# 02-Insence_interface.net
KiCad netlist of a schematic drawn in Altium Designer
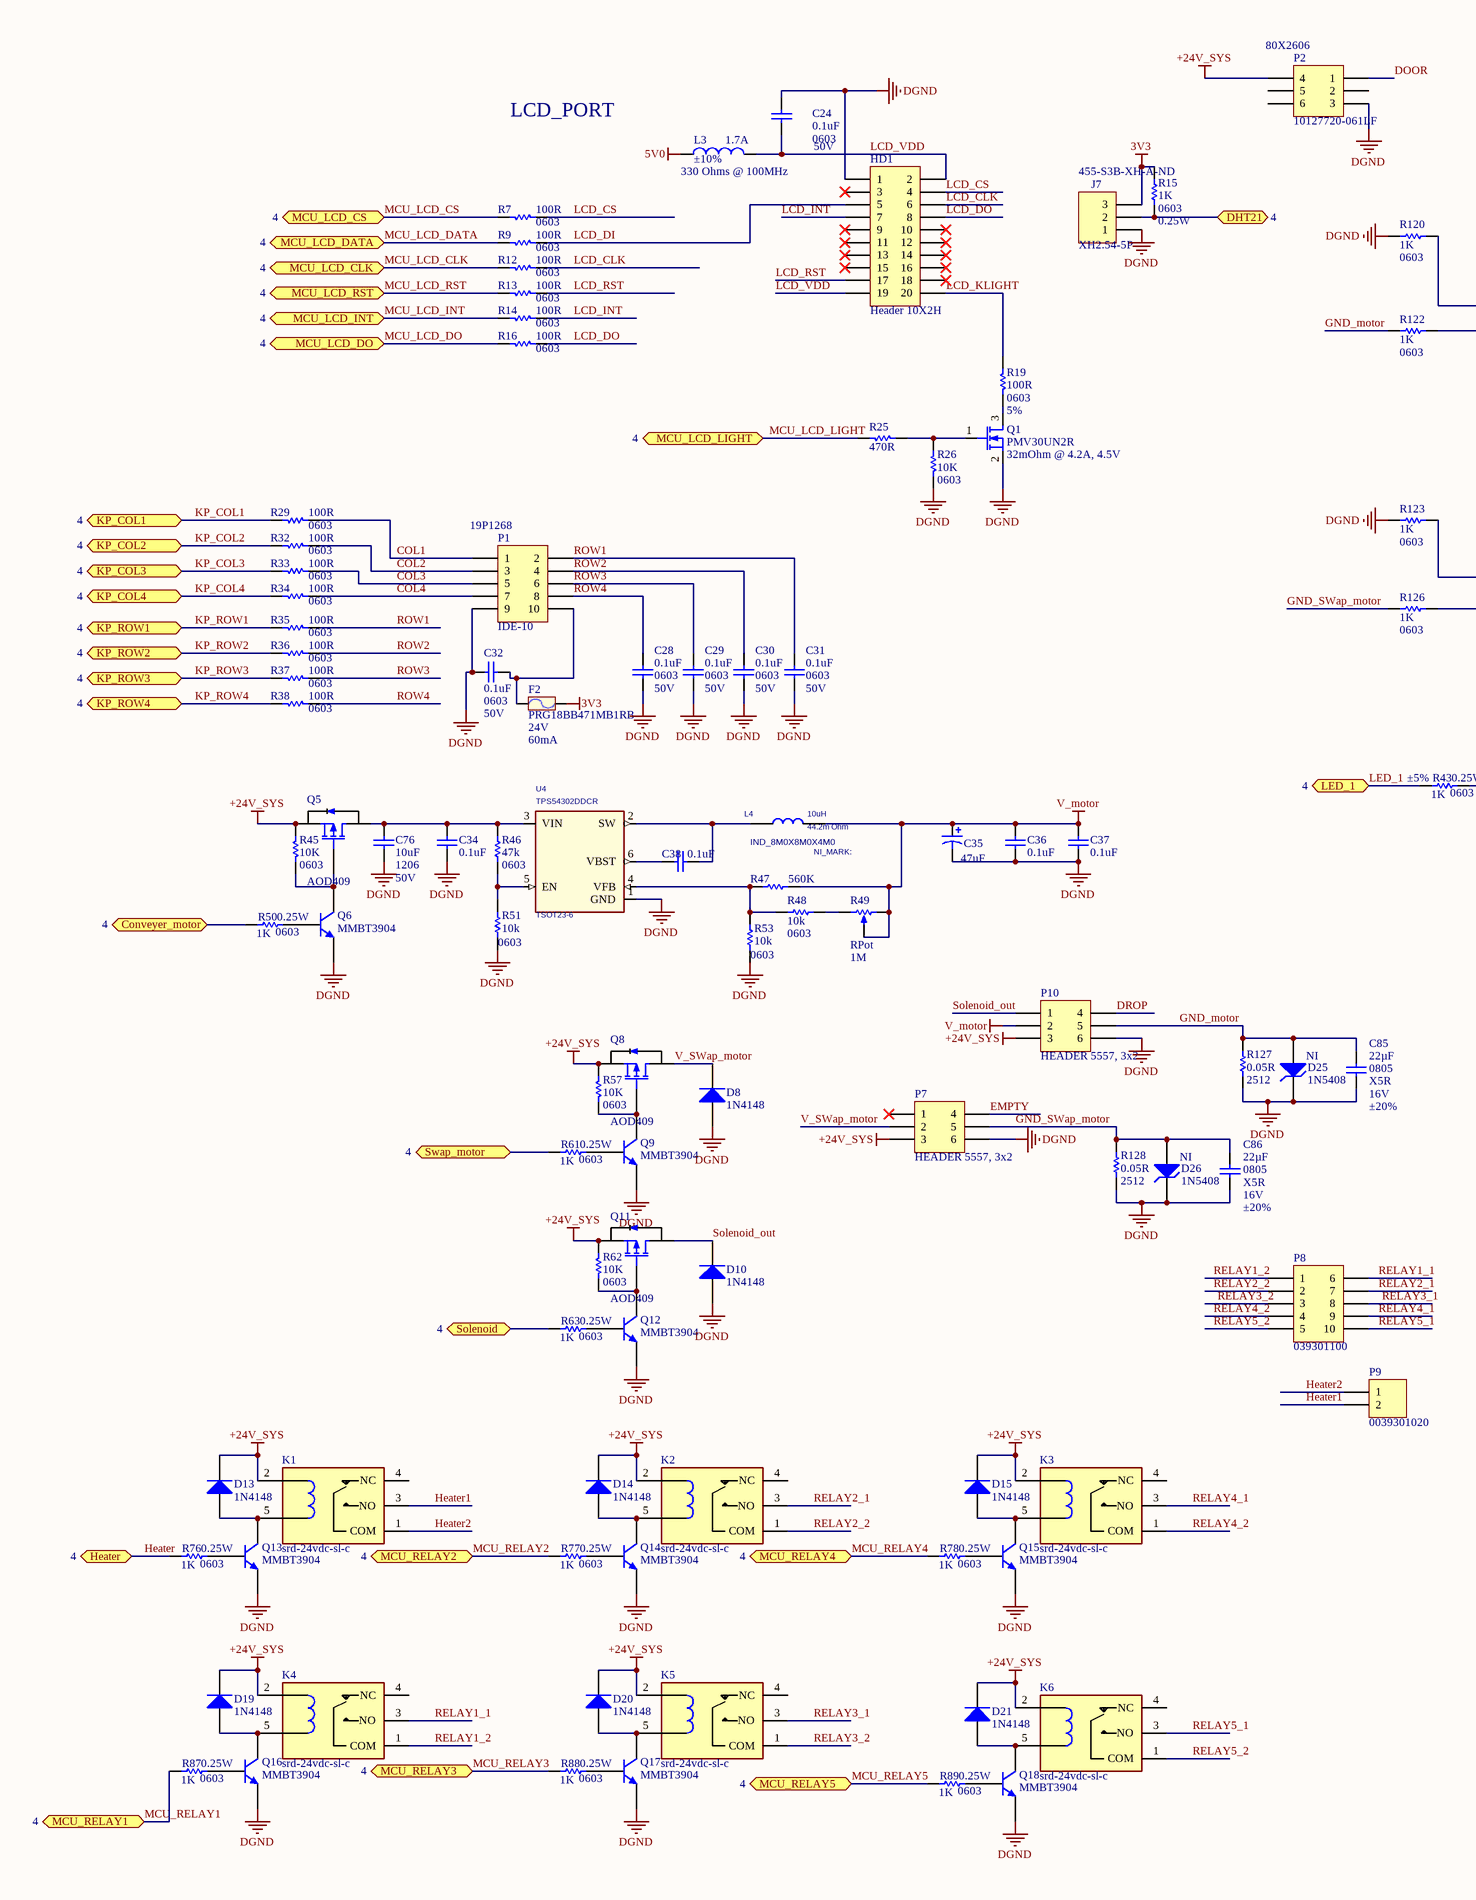
[diagram p0: 02-Insence_interface.SchDoc, left]
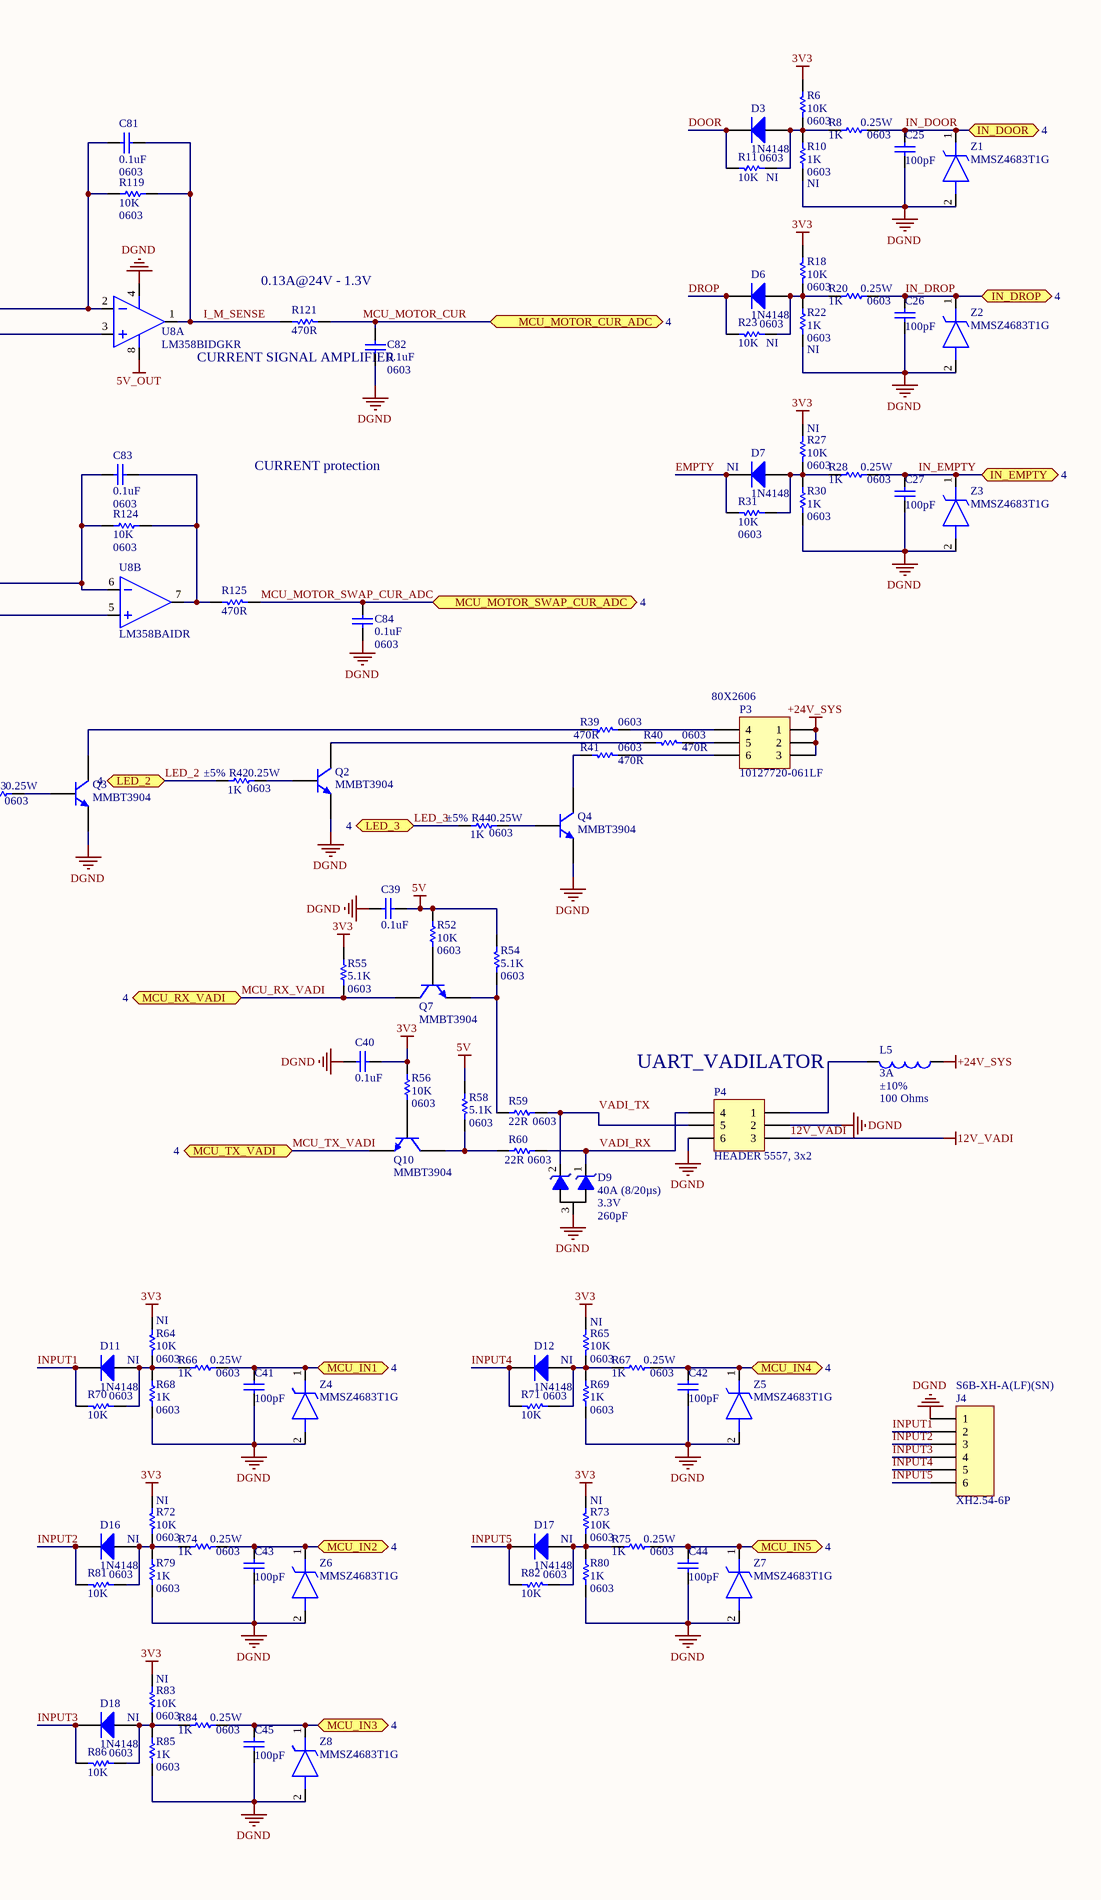
[diagram p1: 02-Insence_interface.SchDoc, right]

(export (version "E")
  (design (tool "Eeschema 10.0.6"))
  (components
    (comp (ref "C24")
      (value "0.1uF")
      (footprint "0603")
      (description "CAP CER 0.1UF 50V X7R 0603")
      (fields
        (field (name "MANUFACTURER1_PART#") "CL10B104KB8NNNC")
        (field (name "VOLTAGE") "50V")
        (field (name "TOLERANCE") "±10%")
      )
      (libsource (lib "thuvien") (part "Cap_0.1uF"))
    )
    (comp (ref "C25")
      (value "100pF")
      (footprint "CAP 0603")
      (description "CAP CER 100PF 50V C0G/NPO 0603")
      (fields (field (name "VOLTAGE") "50V") (field (name "TOLERANCE") "±10%"))
      (libsource (lib "Slider") (part "Cap"))
    )
    (comp (ref "C26")
      (value "100pF")
      (footprint "CAP 0603")
      (description "CAP CER 100PF 50V C0G/NPO 0603")
      (fields (field (name "VOLTAGE") "50V") (field (name "TOLERANCE") "±10%"))
      (libsource (lib "Slider") (part "Cap"))
    )
    (comp (ref "C27")
      (value "100pF")
      (footprint "CAP 0603")
      (description "CAP CER 100PF 50V C0G/NPO 0603")
      (fields (field (name "VOLTAGE") "50V") (field (name "TOLERANCE") "±10%"))
      (libsource (lib "Slider") (part "Cap"))
    )
    (comp (ref "C28")
      (value "0.1uF")
      (footprint "0603")
      (description "CAP CER 0.1UF 50V X7R 0603")
      (fields
        (field (name "MANUFACTURER1_PART#") "CL10B104KB8NNNC")
        (field (name "VOLTAGE") "50V")
        (field (name "TOLERANCE") "±10%")
      )
      (libsource (lib "thuvien") (part "Cap_0.1uF"))
    )
    (comp (ref "C29")
      (value "0.1uF")
      (footprint "0603")
      (description "CAP CER 0.1UF 50V X7R 0603")
      (fields
        (field (name "MANUFACTURER1_PART#") "CL10B104KB8NNNC")
        (field (name "VOLTAGE") "50V")
        (field (name "TOLERANCE") "±10%")
      )
      (libsource (lib "thuvien") (part "Cap_0.1uF"))
    )
    (comp (ref "C30")
      (value "0.1uF")
      (footprint "0603")
      (description "CAP CER 0.1UF 50V X7R 0603")
      (fields
        (field (name "MANUFACTURER1_PART#") "CL10B104KB8NNNC")
        (field (name "VOLTAGE") "50V")
        (field (name "TOLERANCE") "±10%")
      )
      (libsource (lib "thuvien") (part "Cap_0.1uF"))
    )
    (comp (ref "C31")
      (value "0.1uF")
      (footprint "0603")
      (description "CAP CER 0.1UF 50V X7R 0603")
      (fields
        (field (name "MANUFACTURER1_PART#") "CL10B104KB8NNNC")
        (field (name "VOLTAGE") "50V")
        (field (name "TOLERANCE") "±10%")
      )
      (libsource (lib "thuvien") (part "Cap_0.1uF"))
    )
    (comp (ref "C32")
      (value "0.1uF")
      (footprint "0603")
      (description "CAP CER 0.1UF 50V X7R 0603")
      (fields
        (field (name "MANUFACTURER1_PART#") "CL10B104KB8NNNC")
        (field (name "VOLTAGE") "50V")
        (field (name "TOLERANCE") "±10%")
      )
      (libsource (lib "thuvien") (part "Cap_0.1uF"))
    )
    (comp (ref "C34")
      (value "Cap")
      (footprint "0805")
      (description "CAP CER 0.1UF 50V X7R 0603")
      (fields
        (field (name "=VALUE") "0.1uF")
        (field (name "MANUFACTURER1_PART#") "CL10B104KB8NNNC")
        (field (name "PUBLISHER") "Altium Limited")
      )
      (libsource (lib "Miscellaneous Devices") (part "Cap"))
    )
    (comp (ref "C35")
      (value "47uF")
      (footprint "CAP ALUM SMD-D Package 6.3x5.4mm")
      (description "CAP ALUM 47UF 20% 35V SMD")
      (fields
        (field (name "MANUFACTURER1_PART#") "UUR1V470MCL6GS")
        (field (name "MANUFACTURER2_PART#") "EDK476M035A9GAA")
      )
      (libsource (lib "My Library") (part "Cap TANTAN 47UF35V2917"))
    )
    (comp (ref "C36")
      (value "Cap")
      (footprint "0805")
      (description "cap,0805,0.1uF,50V")
      (fields (field (name "=VALUE") "0.1uF") (field (name "PUBLISHER") "Altium Limited"))
      (libsource (lib "Miscellaneous Devices") (part "Cap"))
    )
    (comp (ref "C37")
      (value "Cap")
      (footprint "0805")
      (description "cap,0805,0.1uF,50V")
      (fields (field (name "=VALUE") "0.1uF") (field (name "PUBLISHER") "Altium Limited"))
      (libsource (lib "Miscellaneous Devices") (part "Cap"))
    )
    (comp (ref "C38")
      (value "Cap")
      (footprint "cap 0603")
      (description "CAP CER 0.1UF 50V X7R 0603")
      (fields
        (field (name "=VALUE") "0.1uF")
        (field (name "MANUFACTURER1_PART#") "CL10B104KB8NNNC")
        (field (name "PUBLISHER") "Altium Limited")
      )
      (libsource (lib "Miscellaneous Devices") (part "Cap"))
    )
    (comp (ref "C39")
      (value "0.1uF")
      (footprint "CAP 0603")
      (description "CAP CER 0.1UF 50V X7R 0603")
      (fields (field (name "VOLTAGE") "50V") (field (name "TOLERANCE") "±10%"))
      (libsource (lib "Slider") (part "Cap"))
    )
    (comp (ref "C40")
      (value "0.1uF")
      (footprint "CAP 0603")
      (description "CAP CER 0.1UF 50V X7R 0603")
      (fields (field (name "VOLTAGE") "50V") (field (name "TOLERANCE") "±10%"))
      (libsource (lib "Slider") (part "Cap"))
    )
    (comp (ref "C41")
      (value "100pF")
      (footprint "CAP 0603")
      (description "CAP CER 100PF 50V C0G/NPO 0603")
      (fields (field (name "VOLTAGE") "50V") (field (name "TOLERANCE") "±10%"))
      (libsource (lib "Slider") (part "Cap"))
    )
    (comp (ref "C42")
      (value "100pF")
      (footprint "CAP 0603")
      (description "CAP CER 100PF 50V C0G/NPO 0603")
      (fields (field (name "VOLTAGE") "50V") (field (name "TOLERANCE") "±10%"))
      (libsource (lib "Slider") (part "Cap"))
    )
    (comp (ref "C43")
      (value "100pF")
      (footprint "CAP 0603")
      (description "CAP CER 100PF 50V C0G/NPO 0603")
      (fields (field (name "VOLTAGE") "50V") (field (name "TOLERANCE") "±10%"))
      (libsource (lib "Slider") (part "Cap"))
    )
    (comp (ref "C44")
      (value "100pF")
      (footprint "CAP 0603")
      (description "CAP CER 100PF 50V C0G/NPO 0603")
      (fields (field (name "VOLTAGE") "50V") (field (name "TOLERANCE") "±10%"))
      (libsource (lib "Slider") (part "Cap"))
    )
    (comp (ref "C45")
      (value "100pF")
      (footprint "CAP 0603")
      (description "CAP CER 100PF 50V C0G/NPO 0603")
      (fields (field (name "VOLTAGE") "50V") (field (name "TOLERANCE") "±10%"))
      (libsource (lib "Slider") (part "Cap"))
    )
    (comp (ref "C76")
      (value "10uF")
      (footprint "1206")
      (description "CAP CER 10UF 50V X5R 1206")
      (fields
        (field (name "VOLTAGE") "50V")
        (field (name "TOLERANCE") "±10%")
        (field (name "MANUFACTURER1_PART#") "CL31A106MBHNNNE")
      )
      (libsource (lib "Slider") (part "Cap"))
    )
    (comp (ref "C81")
      (value "0.1uF")
      (footprint "0603")
      (description "CAP CER 0.1UF 50V X7R 0603")
      (fields (field (name "VOLTAGE") "50V") (field (name "TOLERANCE") "±10%"))
      (libsource (lib "Slider") (part "Cap"))
    )
    (comp (ref "C82")
      (value "0.1uF")
      (footprint "0603")
      (description "CAP CER 0.1UF 50V X7R 0603")
      (fields (field (name "VOLTAGE") "50V") (field (name "TOLERANCE") "±10%"))
      (libsource (lib "Slider") (part "Cap"))
    )
    (comp (ref "C83")
      (value "0.1uF")
      (footprint "0603")
      (description "CAP CER 0.1UF 50V X7R 0603")
      (fields (field (name "VOLTAGE") "50V") (field (name "TOLERANCE") "±10%"))
      (libsource (lib "Slider") (part "Cap"))
    )
    (comp (ref "C84")
      (value "0.1uF")
      (footprint "0603")
      (description "CAP CER 0.1UF 50V X7R 0603")
      (fields (field (name "VOLTAGE") "50V") (field (name "TOLERANCE") "±10%"))
      (libsource (lib "Slider") (part "Cap"))
    )
    (comp (ref "C85")
      (value "22µF")
      (footprint "CAP 0805")
      (description "CAP CER 22UF 16V X5R 0805")
      (fields
        (field (name "MANUFACTURER1_PART#") "CL21A226MOCLRNC")
        (field (name "MANUFACTURER2_PART#") "LMK212BBJ226MG-T")
        (field (name "PACKAGE") "0805")
        (field (name "VOLTAGE") "16V")
        (field (name "TOLERANCE") "±20%")
        (field (name "MATERIAL") "X5R")
      )
      (libsource (lib "Full") (part "Cap-NP-100"))
    )
    (comp (ref "C86")
      (value "22µF")
      (footprint "CAP 0805")
      (description "CAP CER 22UF 16V X5R 0805")
      (fields
        (field (name "MANUFACTURER1_PART#") "CL21A226MOCLRNC")
        (field (name "MANUFACTURER2_PART#") "LMK212BBJ226MG-T")
        (field (name "PACKAGE") "0805")
        (field (name "VOLTAGE") "16V")
        (field (name "TOLERANCE") "±20%")
        (field (name "MATERIAL") "X5R")
      )
      (libsource (lib "Full") (part "Cap-NP-100"))
    )
    (comp (ref "D3")
      (value "1N4148")
      (footprint "diode_1206")
      (description "DIODE GP 100V 300MA SOD123 10K")
      (fields
        (field (name "MANUFACTURER1_PART#") "1N4148WQ-13-F")
        (field (name "PUBLISHER") "Altium Limited")
      )
      (libsource (lib "Miscellaneous Devices") (part "Diode"))
    )
    (comp (ref "D6")
      (value "1N4148")
      (footprint "diode_1206")
      (description "DIODE GP 100V 300MA SOD123 10K")
      (fields
        (field (name "MANUFACTURER1_PART#") "1N4148WQ-13-F")
        (field (name "PUBLISHER") "Altium Limited")
      )
      (libsource (lib "Miscellaneous Devices") (part "Diode"))
    )
    (comp (ref "D7")
      (value "1N4148")
      (footprint "diode_1206")
      (description "DIODE GP 100V 300MA SOD123 10K")
      (fields
        (field (name "ASSEMBLY") "NI")
        (field (name "MANUFACTURER1_PART#") "1N4148WQ-13-F")
        (field (name "PUBLISHER") "Altium Limited")
      )
      (libsource (lib "Miscellaneous Devices") (part "Diode"))
    )
    (comp (ref "D8")
      (value "1N4148")
      (footprint "diode_1206")
      (description "DIODE GP 100V 300MA SOD123 10K")
      (fields
        (field (name "MANUFACTURER1_PART#") "1N4148WQ-13-F")
        (field (name "PUBLISHER") "Altium Limited")
      )
      (libsource (lib "Miscellaneous Devices") (part "Diode"))
    )
    (comp (ref "D9")
      (value "SM3.3H-TP")
      (footprint "SOT-23-3")
      (description "3.3V, ESD PROTECTION DEVICES, SO")
      (fields
        (field (name "CURRENT") "40A (8/20µs)")
        (field (name "MANUFACTURER2_PART#") "GSOT03C-E3-08")
        (field (name "POWER") "500W")
        (field (name "VOLTAGE") "3.3V")
        (field (name "JUNCTION CAPACITANCE") "260pF")
      )
      (libsource (lib "My Library") (part "TVS_DUAL_3V3_SOT23"))
    )
    (comp (ref "D10")
      (value "1N4148")
      (footprint "diode_1206")
      (description "DIODE GP 100V 300MA SOD123 10K")
      (fields
        (field (name "MANUFACTURER1_PART#") "1N4148WQ-13-F")
        (field (name "PUBLISHER") "Altium Limited")
      )
      (libsource (lib "Miscellaneous Devices") (part "Diode"))
    )
    (comp (ref "D11")
      (value "1N4148")
      (footprint "diode_1206")
      (description "DIODE GP 100V 300MA SOD123 10K")
      (fields
        (field (name "ASSEMBLY") "NI")
        (field (name "MANUFACTURER1_PART#") "1N4148WQ-13-F")
        (field (name "PUBLISHER") "Altium Limited")
      )
      (libsource (lib "Miscellaneous Devices") (part "Diode"))
    )
    (comp (ref "D12")
      (value "1N4148")
      (footprint "diode_1206")
      (description "DIODE GP 100V 300MA SOD123 10K")
      (fields
        (field (name "ASSEMBLY") "NI")
        (field (name "MANUFACTURER1_PART#") "1N4148WQ-13-F")
        (field (name "PUBLISHER") "Altium Limited")
      )
      (libsource (lib "Miscellaneous Devices") (part "Diode"))
    )
    (comp (ref "D13")
      (value "1N4148")
      (footprint "diode_1206")
      (description "DIODE GP 100V 300MA SOD123 10K")
      (fields
        (field (name "MANUFACTURER1_PART#") "1N4148WQ-13-F")
        (field (name "PUBLISHER") "Altium Limited")
      )
      (libsource (lib "Miscellaneous Devices") (part "Diode"))
    )
    (comp (ref "D14")
      (value "1N4148")
      (footprint "diode_1206")
      (description "DIODE GP 100V 300MA SOD123 10K")
      (fields
        (field (name "MANUFACTURER1_PART#") "1N4148WQ-13-F")
        (field (name "PUBLISHER") "Altium Limited")
      )
      (libsource (lib "Miscellaneous Devices") (part "Diode"))
    )
    (comp (ref "D15")
      (value "1N4148")
      (footprint "diode_1206")
      (description "DIODE GP 100V 300MA SOD123 10K")
      (fields
        (field (name "MANUFACTURER1_PART#") "1N4148WQ-13-F")
        (field (name "PUBLISHER") "Altium Limited")
      )
      (libsource (lib "Miscellaneous Devices") (part "Diode"))
    )
    (comp (ref "D16")
      (value "1N4148")
      (footprint "diode_1206")
      (description "DIODE GP 100V 300MA SOD123 10K")
      (fields
        (field (name "ASSEMBLY") "NI")
        (field (name "MANUFACTURER1_PART#") "1N4148WQ-13-F")
        (field (name "PUBLISHER") "Altium Limited")
      )
      (libsource (lib "Miscellaneous Devices") (part "Diode"))
    )
    (comp (ref "D17")
      (value "1N4148")
      (footprint "diode_1206")
      (description "DIODE GP 100V 300MA SOD123 10K")
      (fields
        (field (name "ASSEMBLY") "NI")
        (field (name "MANUFACTURER1_PART#") "1N4148WQ-13-F")
        (field (name "PUBLISHER") "Altium Limited")
      )
      (libsource (lib "Miscellaneous Devices") (part "Diode"))
    )
    (comp (ref "D18")
      (value "1N4148")
      (footprint "diode_1206")
      (description "DIODE GP 100V 300MA SOD123 10K")
      (fields
        (field (name "ASSEMBLY") "NI")
        (field (name "MANUFACTURER1_PART#") "1N4148WQ-13-F")
        (field (name "PUBLISHER") "Altium Limited")
      )
      (libsource (lib "Miscellaneous Devices") (part "Diode"))
    )
    (comp (ref "D19")
      (value "1N4148")
      (footprint "diode_1206")
      (description "DIODE GP 100V 300MA SOD123 10K")
      (fields
        (field (name "MANUFACTURER1_PART#") "1N4148WQ-13-F")
        (field (name "PUBLISHER") "Altium Limited")
      )
      (libsource (lib "Miscellaneous Devices") (part "Diode"))
    )
    (comp (ref "D20")
      (value "1N4148")
      (footprint "diode_1206")
      (description "DIODE GP 100V 300MA SOD123 10K")
      (fields
        (field (name "MANUFACTURER1_PART#") "1N4148WQ-13-F")
        (field (name "PUBLISHER") "Altium Limited")
      )
      (libsource (lib "Miscellaneous Devices") (part "Diode"))
    )
    (comp (ref "D21")
      (value "1N4148")
      (footprint "diode_1206")
      (description "DIODE GP 100V 300MA SOD123 10K")
      (fields
        (field (name "MANUFACTURER1_PART#") "1N4148WQ-13-F")
        (field (name "PUBLISHER") "Altium Limited")
      )
      (libsource (lib "Miscellaneous Devices") (part "Diode"))
    )
    (comp (ref "D25")
      (value "1N5408")
      (footprint "SMB")
      (description "TVS DIODE 30V 50.82V DO214AB")
      (fields (field (name "MANUFACTURER1_PART#") "S3MHE3_A/I") (field (name "NI_MARK") "NI"))
      (libsource (lib "My Library") (part "Diode Zener"))
    )
    (comp (ref "D26")
      (value "1N5408")
      (footprint "SMB")
      (description "TVS DIODE 30V 50.82V DO214AB")
      (fields (field (name "MANUFACTURER1_PART#") "S3MHE3_A/I") (field (name "NI_MARK") "NI"))
      (libsource (lib "My Library") (part "Diode Zener"))
    )
    (comp (ref "F2")
      (value "PRG18BB471MB1RB")
      (footprint "FB 0603")
      (description "PTC RESET FUSE 24V 10MA 0603")
      (fields (field (name "VOLTAGE - RATED") "24V") (field (name "CURRENT RATING (AMPS)") "60mA"))
      (libsource (lib "power acdc 12v 400mA V05") (part "0875.800MXEP"))
    )
    (comp (ref "HD1")
      (value "Header 10X2H")
      (footprint "IDE_20-RA")
      (description "CONN HEADER R/A 20POS 2.54MM")
      (fields (field (name "MANUFACTURER1_PART#") "61202021721") (field (name "PUBLISHER") "Altium Limited"))
      (libsource (lib "Miscellaneous Connectors") (part "Header 10X2H"))
    )
    (comp (ref "J4")
      (value "XH2.54-6P")
      (footprint "XH2.54-6P-RA")
      (description "CONN HEADER R/A 6POS 2.5MM")
      (fields
        (field (name "SUPPLIER PART NUMBER 1") "S6B-XH-A(LF)(SN)")
        (field (name "MANUFACTURER1_PART#") "S6B-XH-A")
        (field (name "PUBLISHER") "Altium Limited")
      )
      (libsource (lib "Miscellaneous Connectors") (part "Header 6"))
    )
    (comp (ref "J7")
      (value "XH2.54-5P")
      (footprint "XH2.54-3P-RA")
      (description "CONN HEADER R/A 3POS 2.5MM")
      (fields
        (field (name "SUPPLIER PART NUMBER 1") "455-S3B-XH-A-ND")
        (field (name "MANUFACTURER1_PART#") "S3B-XH-A")
        (field (name "PUBLISHER") "Altium Limited")
      )
      (libsource (lib "Miscellaneous Connectors") (part "Header 3"))
    )
    (comp (ref "K1")
      (value "srd-24vdc-sl-c")
      (footprint "Hiendv:srd24vdcslc")
      (description "Relay 24V 10A 5 PIN")
      (libsource (lib "lib") (part "srd-24vdc-sl-c"))
    )
    (comp (ref "K2")
      (value "srd-24vdc-sl-c")
      (footprint "Hiendv:srd24vdcslc")
      (description "Relay 24V 10A 5 PIN")
      (libsource (lib "lib") (part "srd-24vdc-sl-c"))
    )
    (comp (ref "K3")
      (value "srd-24vdc-sl-c")
      (footprint "Hiendv:srd24vdcslc")
      (description "Relay 24V 10A 5 PIN")
      (libsource (lib "lib") (part "srd-24vdc-sl-c"))
    )
    (comp (ref "K4")
      (value "srd-24vdc-sl-c")
      (footprint "Hiendv:srd24vdcslc")
      (description "Relay 24V 10A 5 PIN")
      (libsource (lib "lib") (part "srd-24vdc-sl-c"))
    )
    (comp (ref "K5")
      (value "srd-24vdc-sl-c")
      (footprint "Hiendv:srd24vdcslc")
      (description "Relay 24V 10A 5 PIN")
      (libsource (lib "lib") (part "srd-24vdc-sl-c"))
    )
    (comp (ref "K6")
      (value "srd-24vdc-sl-c")
      (footprint "Hiendv:srd24vdcslc")
      (description "Relay 24V 10A 5 PIN")
      (libsource (lib "lib") (part "srd-24vdc-sl-c"))
    )
    (comp (ref "L3")
      (value "330 Ohms @ 100MHz")
      (footprint "FB 0603")
      (description "FERRITE BEAD 330 OHM 0603 1LN")
      (fields
        (field (name "MANUFACTURER1_PART#") "MPZ1608S331ATA00")
        (field (name "MANUFACTURER2_PART#") "BLM18KG331SN1D")
        (field (name "CURRENT") "1.7A")
        (field (name "TOLERANCE") "±10%")
      )
      (libsource (lib "Full") (part "inductor 2.2uF"))
    )
    (comp (ref "L4")
      (value "10uH")
      (footprint "IND 8x8MM")
      (description "IND-SMD;10uH,20%,8x8x4mm,3.1A,44.2mOHM")
      (fields
        (field (name "PACKAGE") "IND_8M0X8M0X4M0")
        (field (name "TOLERANCE") "20%")
        (field (name "MFG1_PART#") "NR8040T100M")
        (field (name "DCR") "44.2m Ohm")
        (field (name "BY") "VINFAST_RD")
      )
      (libsource (lib "*") (part "IND_10uH_3.1A_44.2mOhm_8MX8MX4M"))
    )
    (comp (ref "L5")
      (value "100 Ohms")
      (footprint "FB 0603")
      (description "FERRITE BEAD 100 OHM 0603 1LN")
      (fields
        (field (name "MANUFACTURER1_PART#") "MPZ1608S101ATAH0")
        (field (name "MANUFACTURER2_PART#") "BLM18KG101TN1D")
        (field (name "CURRENT") "3A")
        (field (name "TOLERANCE") "±10%")
      )
      (libsource (lib "Full") (part "inductor 2.2uF"))
    )
    (comp (ref "P1")
      (value "IDE-10")
      (footprint "IDE-10-RA")
      (description "CONN HEADER R/A 10POS 2.54MM")
      (fields
        (field (name "MANUFACTURER1_PART#") "61201021721")
        (field (name "SUPPLIER PART NUMBER 1") "19P1268")
      )
      (libsource (lib "My Library") (part "IDE10"))
    )
    (comp (ref "P2")
      (value "10127720-061LF")
      (footprint "PHM-3x2H 3.0 - RA")
      (description "Header, 3-Pin, Dual row")
      (fields (field (name "SUPPLIER PART NUMBER 1") "80X2606") (field (name "PUBLISHER") "Altium Limited"))
      (libsource (lib "Miscellaneous Connectors") (part "Header 3X2A"))
    )
    (comp (ref "P3")
      (value "10127720-061LF")
      (footprint "PHM-3x2H 3.0 - RA")
      (description "Header, 3-Pin, Dual row")
      (fields (field (name "SUPPLIER PART NUMBER 1") "80X2606") (field (name "PUBLISHER") "Altium Limited"))
      (libsource (lib "Miscellaneous Connectors") (part "Header 3X2A"))
    )
    (comp (ref "P4")
      (value "HEADER 5557, 3x2")
      (footprint "HDR2x3 4_2MM FEMALE TH RA")
      (description "CONN HEADER R/A 6POS 4.2MM")
      (fields (field (name "MANUFACTURER1_PART#") "0039301060") (field (name "PUBLISHER") "Altium Limited"))
      (libsource (lib "Miscellaneous Connectors") (part "Header 3X2A"))
    )
    (comp (ref "P7")
      (value "HEADER 5557, 3x2")
      (footprint "HDR2x3 4_2MM FEMALE TH RA")
      (description "CONN HEADER R/A 6POS 4.2MM")
      (fields (field (name "MANUFACTURER1_PART#") "0039301060") (field (name "PUBLISHER") "Altium Limited"))
      (libsource (lib "") (part "Header 3X2A_1"))
    )
    (comp (ref "P8")
      (value "039301100")
      (footprint "HDR2x5 4_2MM FEMALE TH RA")
      (description "CONN HEADER R/A 10POS 4.2MM")
      (fields (field (name "PUBLISHER") "Altium Limited"))
      (libsource (lib "Miscellaneous Connectors") (part "Header 5X2A"))
    )
    (comp (ref "P9")
      (value "0039301020")
      (footprint "HDR2x1 4_2MM FEMALE TH RA")
      (description "Header, 2-Pin, Right Angle")
      (fields (field (name "PUBLISHER") "Altium Limited"))
      (libsource (lib "Miscellaneous Connectors") (part "Header 2H"))
    )
    (comp (ref "P10")
      (value "HEADER 5557, 3x2")
      (footprint "HDR2x3 4_2MM FEMALE TH RA")
      (description "CONN HEADER R/A 6POS 4.2MM")
      (fields (field (name "MANUFACTURER1_PART#") "0039301060") (field (name "PUBLISHER") "Altium Limited"))
      (libsource (lib "") (part "Header 3X2A_1"))
    )
    (comp (ref "Q1")
      (value "PMV30UN2R")
      (footprint "SOT-23-3")
      (description "MOSFET N-CH 20V 4.2A SOT23")
      (fields (field (name "RDSON") "32mOhm @ 4.2A, 4.5V"))
      (libsource (lib "VSM_SES-MAIN_REV04B") (part "Si2302DS"))
    )
    (comp (ref "Q2")
      (value "MMBT3904")
      (footprint "SOT-23")
      (description "NPN 200mA 40V 350mW SOT-23 Transistors")
      (libsource (lib "Miscellaneous Devices") (part "NPN"))
    )
    (comp (ref "Q3")
      (value "MMBT3904")
      (footprint "SOT-23")
      (description "NPN 200mA 40V 350mW SOT-23 Transistors")
      (libsource (lib "Miscellaneous Devices") (part "NPN"))
    )
    (comp (ref "Q4")
      (value "MMBT3904")
      (footprint "SOT-23")
      (description "NPN 200mA 40V 350mW SOT-23 Transistors")
      (libsource (lib "Miscellaneous Devices") (part "NPN"))
    )
    (comp (ref "Q5")
      (value "AOD409")
      (footprint "TO-252")
      (description "MOSFET P-CH 60V 26A TO252")
      (fields (field (name "PUBLISHER") "Altium Limited"))
      (libsource (lib "lib") (part "MOSFET-P"))
    )
    (comp (ref "Q6")
      (value "MMBT3904")
      (footprint "SOT-23")
      (description "NPN 200mA 40V 350mW SOT-23 Transistors")
      (libsource (lib "Miscellaneous Devices") (part "NPN"))
    )
    (comp (ref "Q7")
      (value "MMBT3904")
      (footprint "SOT-23")
      (description "NPN 200mA 40V 350mW SOT-23 Transistors")
      (libsource (lib "") (part "NPN_1"))
    )
    (comp (ref "Q8")
      (value "AOD409")
      (footprint "TO-252")
      (description "MOSFET P-CH 60V 26A TO252")
      (fields (field (name "PUBLISHER") "Altium Limited"))
      (libsource (lib "lib") (part "MOSFET-P"))
    )
    (comp (ref "Q9")
      (value "MMBT3904")
      (footprint "SOT-23")
      (description "NPN 200mA 40V 350mW SOT-23 Transistors")
      (libsource (lib "Miscellaneous Devices") (part "NPN"))
    )
    (comp (ref "Q10")
      (value "MMBT3904")
      (footprint "SOT-23")
      (description "NPN 200mA 40V 350mW SOT-23 Transistors")
      (libsource (lib "") (part "NPN_1"))
    )
    (comp (ref "Q11")
      (value "AOD409")
      (footprint "TO-252")
      (description "MOSFET P-CH 60V 26A TO252")
      (fields (field (name "PUBLISHER") "Altium Limited"))
      (libsource (lib "lib") (part "MOSFET-P"))
    )
    (comp (ref "Q12")
      (value "MMBT3904")
      (footprint "SOT-23")
      (description "NPN 200mA 40V 350mW SOT-23 Transistors")
      (libsource (lib "Miscellaneous Devices") (part "NPN"))
    )
    (comp (ref "Q13")
      (value "MMBT3904")
      (footprint "SOT-23")
      (description "NPN 200mA 40V 350mW SOT-23 Transistors")
      (libsource (lib "Miscellaneous Devices") (part "NPN"))
    )
    (comp (ref "Q14")
      (value "MMBT3904")
      (footprint "SOT-23")
      (description "NPN 200mA 40V 350mW SOT-23 Transistors")
      (libsource (lib "Miscellaneous Devices") (part "NPN"))
    )
    (comp (ref "Q15")
      (value "MMBT3904")
      (footprint "SOT-23")
      (description "NPN 200mA 40V 350mW SOT-23 Transistors")
      (libsource (lib "Miscellaneous Devices") (part "NPN"))
    )
    (comp (ref "Q16")
      (value "MMBT3904")
      (footprint "SOT-23")
      (description "NPN 200mA 40V 350mW SOT-23 Transistors")
      (libsource (lib "Miscellaneous Devices") (part "NPN"))
    )
    (comp (ref "Q17")
      (value "MMBT3904")
      (footprint "SOT-23")
      (description "NPN 200mA 40V 350mW SOT-23 Transistors")
      (libsource (lib "Miscellaneous Devices") (part "NPN"))
    )
    (comp (ref "Q18")
      (value "MMBT3904")
      (footprint "SOT-23")
      (description "NPN 200mA 40V 350mW SOT-23 Transistors")
      (libsource (lib "Miscellaneous Devices") (part "NPN"))
    )
    (comp (ref "R6")
      (value "10K")
      (footprint "res 0603")
      (description "RES SMD,10K OHM 5% 1/10W 0603")
      (fields
        (field (name "MANUFACTURER1_PART#") "RMCF0603JT10K0")
        (field (name "MANUFACTURER2_PART#") "R0603J10KKDX")
        (field (name "PCB FOOTPRINT") "0603")
      )
      (libsource (lib "altium-import") (part "root_3_mirrored_Res0.3_"))
    )
    (comp (ref "R7")
      (value "100R")
      (footprint "res 0603")
      (description "RES 100 OHM 5% 1/10W 0603")
      (fields (field (name "MANUFACTURER1_PART#") "RMCF0603JG100R") (field (name "PCB_ FOOTPRINT") "0603"))
      (libsource (lib "thuvien") (part "RES 120 OHM 5% 1/10W 0603"))
    )
    (comp (ref "R8")
      (value "1K")
      (footprint "res 0603")
      (description "RES SMD,1K OHM,5%,1/10W,0603")
      (fields
        (field (name "MANUFACTURER1_PART#") "RMCF06031K00JNEAC")
        (field (name "MANUFACTURER2_PART#") "R0603J1KTG")
        (field (name "PCB FOOTPRINT") "0603")
        (field (name "POWER") "0.25W")
      )
      (libsource (lib "Full") (part "Res0.3"))
    )
    (comp (ref "R9")
      (value "100R")
      (footprint "res 0603")
      (description "RES 100 OHM 5% 1/10W 0603")
      (fields (field (name "MANUFACTURER1_PART#") "RMCF0603JG100R") (field (name "PCB_ FOOTPRINT") "0603"))
      (libsource (lib "thuvien") (part "RES 120 OHM 5% 1/10W 0603"))
    )
    (comp (ref "R10")
      (value "1K")
      (footprint "res 0603")
      (description "RES SMD,1K OHM,5%,1/10W,0603")
      (fields
        (field (name "MANUFACTURER1_PART#") "RMCF06031K00JNEAC")
        (field (name "MANUFACTURER2_PART#") "R0603J1KTG")
        (field (name "PCB FOOTPRINT") "0603")
        (field (name "ASSEMBLY") "NI")
      )
      (libsource (lib "Full") (part "Res0.3"))
    )
    (comp (ref "R11")
      (value "10K")
      (footprint "res 0603")
      (description "RES SMD,10K OHM 5% 1/10W 0603")
      (fields
        (field (name "MANUFACTURER1_PART#") "RMCF0603JT10K0")
        (field (name "MANUFACTURER2_PART#") "R0603J10KKDX")
        (field (name "PCB FOOTPRINT") "0603")
        (field (name "ASSEMBLY") "NI")
      )
      (libsource (lib "altium-import") (part "root_2_mirrored_Res0.3_"))
    )
    (comp (ref "R12")
      (value "100R")
      (footprint "res 0603")
      (description "RES 100 OHM 5% 1/10W 0603")
      (fields (field (name "MANUFACTURER1_PART#") "RMCF0603JG100R") (field (name "PCB_ FOOTPRINT") "0603"))
      (libsource (lib "thuvien") (part "RES 120 OHM 5% 1/10W 0603"))
    )
    (comp (ref "R13")
      (value "100R")
      (footprint "res 0603")
      (description "RES 100 OHM 5% 1/10W 0603")
      (fields (field (name "MANUFACTURER1_PART#") "RMCF0603JG100R") (field (name "PCB_ FOOTPRINT") "0603"))
      (libsource (lib "thuvien") (part "RES 120 OHM 5% 1/10W 0603"))
    )
    (comp (ref "R14")
      (value "100R")
      (footprint "res 0603")
      (description "RES 100 OHM 5% 1/10W 0603")
      (fields (field (name "MANUFACTURER1_PART#") "RMCF0603JG100R") (field (name "PCB_ FOOTPRINT") "0603"))
      (libsource (lib "thuvien") (part "RES 120 OHM 5% 1/10W 0603"))
    )
    (comp (ref "R15")
      (value "1K")
      (footprint "res 0603")
      (description "RES SMD,1K OHM,5%,1/10W,0603")
      (fields
        (field (name "MANUFACTURER1_PART#") "RMCF06031K00JNEAC")
        (field (name "MANUFACTURER2_PART#") "R0603J1KTG")
        (field (name "PCB FOOTPRINT") "0603")
        (field (name "POWER") "0.25W")
      )
      (libsource (lib "Full") (part "Res0.3"))
    )
    (comp (ref "R16")
      (value "100R")
      (footprint "res 0603")
      (description "RES 100 OHM 5% 1/10W 0603")
      (fields (field (name "MANUFACTURER1_PART#") "RMCF0603JG100R") (field (name "PCB_ FOOTPRINT") "0603"))
      (libsource (lib "thuvien") (part "RES 120 OHM 5% 1/10W 0603"))
    )
    (comp (ref "R18")
      (value "10K")
      (footprint "res 0603")
      (description "RES SMD,10K OHM 5% 1/10W 0603")
      (fields
        (field (name "MANUFACTURER1_PART#") "RMCF0603JT10K0")
        (field (name "MANUFACTURER2_PART#") "R0603J10KKDX")
        (field (name "PCB FOOTPRINT") "0603")
      )
      (libsource (lib "altium-import") (part "root_3_mirrored_Res0.3_"))
    )
    (comp (ref "R19")
      (value "100R")
      (footprint "res 0603")
      (description "RES 100 OHM 5% 1/10W 0603")
      (fields
        (field (name "MANUFACTURER1_PART#") "RMCF0603JG100R")
        (field (name "PCB_ FOOTPRINT") "0603")
        (field (name "TOLERANCE") "5%")
      )
      (libsource (lib "thuvien") (part "RES 120 OHM 5% 1/10W 0603"))
    )
    (comp (ref "R20")
      (value "1K")
      (footprint "res 0603")
      (description "RES SMD,1K OHM,5%,1/10W,0603")
      (fields
        (field (name "MANUFACTURER1_PART#") "RMCF06031K00JNEAC")
        (field (name "MANUFACTURER2_PART#") "R0603J1KTG")
        (field (name "PCB FOOTPRINT") "0603")
        (field (name "POWER") "0.25W")
      )
      (libsource (lib "Full") (part "Res0.3"))
    )
    (comp (ref "R22")
      (value "1K")
      (footprint "res 0603")
      (description "RES SMD,1K OHM,5%,1/10W,0603")
      (fields
        (field (name "MANUFACTURER1_PART#") "RMCF06031K00JNEAC")
        (field (name "MANUFACTURER2_PART#") "R0603J1KTG")
        (field (name "PCB FOOTPRINT") "0603")
        (field (name "ASSEMBLY") "NI")
      )
      (libsource (lib "Full") (part "Res0.3"))
    )
    (comp (ref "R23")
      (value "10K")
      (footprint "res 0603")
      (description "RES SMD,10K OHM 5% 1/10W 0603")
      (fields
        (field (name "MANUFACTURER1_PART#") "RMCF0603JT10K0")
        (field (name "MANUFACTURER2_PART#") "R0603J10KKDX")
        (field (name "PCB FOOTPRINT") "0603")
        (field (name "ASSEMBLY") "NI")
      )
      (libsource (lib "altium-import") (part "root_2_mirrored_Res0.3_"))
    )
    (comp (ref "R25")
      (value "470R")
      (footprint "res 0603")
      (description "RES SMD, 470 OHM 5% 1/8W 0603")
      (fields
        (field (name "MANUFACTURER1_PART#") "RK73B1JTTD471J")
        (field (name "MANUFACTURER2_PART#") "RMCF0603JT470R")
      )
      (libsource (lib "Full") (part "Res0.3"))
    )
    (comp (ref "R26")
      (value "10K")
      (footprint "res 0603")
      (description "RES SMD,10K OHM 5% 1/10W 0603")
      (fields
        (field (name "MANUFACTURER1_PART#") "RMCF0603JT10K0")
        (field (name "MANUFACTURER2_PART#") "R0603J10KKDX")
        (field (name "PCB FOOTPRINT") "0603")
      )
      (libsource (lib "altium-import") (part "root_3_mirrored_Res0.3_"))
    )
    (comp (ref "R27")
      (value "10K")
      (footprint "res 0603")
      (description "RES SMD,10K OHM 5% 1/10W 0603")
      (fields
        (field (name "MANUFACTURER1_PART#") "RMCF0603JT10K0")
        (field (name "MANUFACTURER2_PART#") "R0603J10KKDX")
        (field (name "PCB FOOTPRINT") "0603")
        (field (name "ASEMBLY") "NI")
      )
      (libsource (lib "altium-import") (part "root_3_mirrored_Res0.3_"))
    )
    (comp (ref "R28")
      (value "1K")
      (footprint "res 0603")
      (description "RES SMD,1K OHM,5%,1/10W,0603")
      (fields
        (field (name "MANUFACTURER1_PART#") "RMCF06031K00JNEAC")
        (field (name "MANUFACTURER2_PART#") "R0603J1KTG")
        (field (name "PCB FOOTPRINT") "0603")
        (field (name "POWER") "0.25W")
      )
      (libsource (lib "Full") (part "Res0.3"))
    )
    (comp (ref "R29")
      (value "100R")
      (footprint "res 0603")
      (description "RES 100 OHM 5% 1/10W 0603")
      (fields (field (name "MANUFACTURER1_PART#") "RMCF0603JG100R") (field (name "PCB_ FOOTPRINT") "0603"))
      (libsource (lib "thuvien") (part "RES 120 OHM 5% 1/10W 0603"))
    )
    (comp (ref "R30")
      (value "1K")
      (footprint "res 0603")
      (description "RES SMD,1K OHM,5%,1/10W,0603")
      (fields
        (field (name "MANUFACTURER1_PART#") "RMCF06031K00JNEAC")
        (field (name "MANUFACTURER2_PART#") "R0603J1KTG")
        (field (name "PCB FOOTPRINT") "0603")
      )
      (libsource (lib "Full") (part "Res0.3"))
    )
    (comp (ref "R31")
      (value "10K")
      (footprint "res 0603")
      (description "RES SMD,10K OHM 5% 1/10W 0603")
      (fields
        (field (name "MANUFACTURER1_PART#") "RMCF0603JT10K0")
        (field (name "MANUFACTURER2_PART#") "R0603J10KKDX")
        (field (name "PCB FOOTPRINT") "0603")
      )
      (libsource (lib "altium-import") (part "root_2_mirrored_Res0.3_"))
    )
    (comp (ref "R32")
      (value "100R")
      (footprint "res 0603")
      (description "RES 100 OHM 5% 1/10W 0603")
      (fields (field (name "MANUFACTURER1_PART#") "RMCF0603JG100R") (field (name "PCB_ FOOTPRINT") "0603"))
      (libsource (lib "thuvien") (part "RES 120 OHM 5% 1/10W 0603"))
    )
    (comp (ref "R33")
      (value "100R")
      (footprint "res 0603")
      (description "RES 100 OHM 5% 1/10W 0603")
      (fields (field (name "MANUFACTURER1_PART#") "RMCF0603JG100R") (field (name "PCB_ FOOTPRINT") "0603"))
      (libsource (lib "thuvien") (part "RES 120 OHM 5% 1/10W 0603"))
    )
    (comp (ref "R34")
      (value "100R")
      (footprint "res 0603")
      (description "RES 100 OHM 5% 1/10W 0603")
      (fields (field (name "MANUFACTURER1_PART#") "RMCF0603JG100R") (field (name "PCB_ FOOTPRINT") "0603"))
      (libsource (lib "thuvien") (part "RES 120 OHM 5% 1/10W 0603"))
    )
    (comp (ref "R35")
      (value "100R")
      (footprint "res 0603")
      (description "RES 100 OHM 5% 1/10W 0603")
      (fields (field (name "MANUFACTURER1_PART#") "RMCF0603JG100R") (field (name "PCB_ FOOTPRINT") "0603"))
      (libsource (lib "thuvien") (part "RES 120 OHM 5% 1/10W 0603"))
    )
    (comp (ref "R36")
      (value "100R")
      (footprint "res 0603")
      (description "RES 100 OHM 5% 1/10W 0603")
      (fields (field (name "MANUFACTURER1_PART#") "RMCF0603JG100R") (field (name "PCB_ FOOTPRINT") "0603"))
      (libsource (lib "thuvien") (part "RES 120 OHM 5% 1/10W 0603"))
    )
    (comp (ref "R37")
      (value "100R")
      (footprint "res 0603")
      (description "RES 100 OHM 5% 1/10W 0603")
      (fields (field (name "MANUFACTURER1_PART#") "RMCF0603JG100R") (field (name "PCB_ FOOTPRINT") "0603"))
      (libsource (lib "thuvien") (part "RES 120 OHM 5% 1/10W 0603"))
    )
    (comp (ref "R38")
      (value "100R")
      (footprint "res 0603")
      (description "RES 100 OHM 5% 1/10W 0603")
      (fields (field (name "MANUFACTURER1_PART#") "RMCF0603JG100R") (field (name "PCB_ FOOTPRINT") "0603"))
      (libsource (lib "thuvien") (part "RES 120 OHM 5% 1/10W 0603"))
    )
    (comp (ref "R39")
      (value "470R")
      (footprint "res 0603")
      (description "RES SMD, 470 OHM 5% 1/8W 0603")
      (fields
        (field (name "MANUFACTURER1_PART#") "RK73B1JTTD471J")
        (field (name "MANUFACTURER2_PART#") "RMCF0603JT470R")
        (field (name "PCB FOOTPRINT") "0603")
      )
      (libsource (lib "Full") (part "Res0.3"))
    )
    (comp (ref "R40")
      (value "470R")
      (footprint "res 0603")
      (description "RES SMD, 470 OHM 5% 1/8W 0603")
      (fields
        (field (name "MANUFACTURER1_PART#") "RK73B1JTTD471J")
        (field (name "MANUFACTURER2_PART#") "RMCF0603JT470R")
        (field (name "PCB FOOTPRINT") "0603")
      )
      (libsource (lib "Full") (part "Res0.3"))
    )
    (comp (ref "R41")
      (value "470R")
      (footprint "res 0603")
      (description "RES SMD, 470 OHM 5% 1/8W 0603")
      (fields
        (field (name "MANUFACTURER1_PART#") "RK73B1JTTD471J")
        (field (name "MANUFACTURER2_PART#") "RMCF0603JT470R")
        (field (name "PCB FOOTPRINT") "0603")
      )
      (libsource (lib "Full") (part "Res0.3"))
    )
    (comp (ref "R42")
      (value "1K")
      (footprint "res 0603")
      (description "RES SMD,1K OHM,5%,1/10W,0603")
      (fields
        (field (name "MANUFACTURER1_PART#") "RMCF06031K00JNEAC")
        (field (name "MANUFACTURER2_PART#") "R0603J1KTG")
        (field (name "PCB FOOTPRINT") "0603")
        (field (name "POWER") "0.25W")
        (field (name "TOLERANCE") "±5%")
      )
      (libsource (lib "Full") (part "Res0.3"))
    )
    (comp (ref "R43")
      (value "1K")
      (footprint "res 0603")
      (description "RES SMD,1K OHM,5%,1/10W,0603")
      (fields
        (field (name "MANUFACTURER1_PART#") "RMCF06031K00JNEAC")
        (field (name "MANUFACTURER2_PART#") "R0603J1KTG")
        (field (name "PCB FOOTPRINT") "0603")
        (field (name "POWER") "0.25W")
        (field (name "TOLERANCE") "±5%")
      )
      (libsource (lib "Full") (part "Res0.3"))
    )
    (comp (ref "R44")
      (value "1K")
      (footprint "res 0603")
      (description "RES SMD,1K OHM,5%,1/10W,0603")
      (fields
        (field (name "MANUFACTURER1_PART#") "RMCF06031K00JNEAC")
        (field (name "MANUFACTURER2_PART#") "R0603J1KTG")
        (field (name "PCB FOOTPRINT") "0603")
        (field (name "POWER") "0.25W")
        (field (name "TOLERANCE") "±5%")
      )
      (libsource (lib "Full") (part "Res0.3"))
    )
    (comp (ref "R45")
      (value "10K")
      (footprint "res 0603")
      (description "RES SMD,10K OHM 5% 1/10W 0603")
      (fields
        (field (name "MANUFACTURER1_PART#") "RMCF0603JT10K0")
        (field (name "MANUFACTURER2_PART#") "R0603J10KKDX")
        (field (name "PCB FOOTPRINT") "0603")
      )
      (libsource (lib "altium-import") (part "root_3_mirrored_Res0.3_"))
    )
    (comp (ref "R46")
      (value "47k")
      (footprint "0603")
      (description "RES 47K OHM 5% 1/10W 0603")
      (fields
        (field (name "MANUFACTURER1_PART#") "RMCF0603JT47K0")
        (field (name "Comment") "Res1")
        (field (name "PUBLISHER") "Altium Limited")
      )
      (libsource (lib "Miscellaneous Devices") (part "Res1"))
    )
    (comp (ref "R47")
      (value "560K")
      (footprint "res 0603")
      (description "RES 560K OHM 1% 1/10W 0603")
      (fields
        (field (name "MANUFACTURER1_PART#") "RC0603FR-07560KL")
        (field (name "Comment") "Res1")
        (field (name "PUBLISHER") "Altium Limited")
      )
      (libsource (lib "Miscellaneous Devices") (part "Res1"))
    )
    (comp (ref "R48")
      (value "10k")
      (footprint "0603")
      (description "RES SMD,10K OHM 5% 1/10W 0603")
      (fields
        (field (name "MANUFACTURER1_PART#") "RMCF0603JT10K0")
        (field (name "Comment") "Res1")
        (field (name "PUBLISHER") "Altium Limited")
      )
      (libsource (lib "Miscellaneous Devices") (part "Res1"))
    )
    (comp (ref "R49")
      (value "RPot")
      (footprint "VR5")
      (description "VR 105-1M 3296W")
      (fields (field (name "ALTIUM_VALUE") "1M") (field (name "PUBLISHER") "Altium Limited"))
      (libsource (lib "Miscellaneous Devices") (part "RPot"))
    )
    (comp (ref "R50")
      (value "1K")
      (footprint "res 0603")
      (description "RES SMD,1K OHM,5%,1/10W,0603")
      (fields
        (field (name "MANUFACTURER1_PART#") "RMCF06031K00JNEAC")
        (field (name "MANUFACTURER2_PART#") "R0603J1KTG")
        (field (name "PCB FOOTPRINT") "0603")
        (field (name "POWER") "0.25W")
      )
      (libsource (lib "Full") (part "Res0.3"))
    )
    (comp (ref "R51")
      (value "10k")
      (footprint "0603")
      (description "RES SMD,10K OHM 5% 1/10W 0603")
      (fields
        (field (name "MANUFACTURER1_PART#") "RMCF0603JT10K0")
        (field (name "Comment") "Res1")
        (field (name "PUBLISHER") "Altium Limited")
      )
      (libsource (lib "Miscellaneous Devices") (part "Res1"))
    )
    (comp (ref "R52")
      (value "10K")
      (footprint "res 0603")
      (description "RES SMD,10K OHM 5% 1/10W 0603")
      (fields
        (field (name "MANUFACTURER1_PART#") "RMCF0603JT10K0")
        (field (name "MANUFACTURER2_PART#") "R0603J10KKDX")
        (field (name "PCB FOOTPRINT") "0603")
      )
      (libsource (lib "altium-import") (part "root_3_Res0.3_"))
    )
    (comp (ref "R53")
      (value "10k")
      (footprint "0603")
      (description "RES SMD,10K OHM 5% 1/10W 0603")
      (fields
        (field (name "MANUFACTURER1_PART#") "RMCF0603JT10K0")
        (field (name "Comment") "Res1")
        (field (name "PUBLISHER") "Altium Limited")
      )
      (libsource (lib "Miscellaneous Devices") (part "Res1"))
    )
    (comp (ref "R54")
      (value "5.1K")
      (footprint "res 0603")
      (description "RES SMD 5.1K OHM 1% 1/10W 0603")
      (fields (field (name "MANUFACTURER1_PART#") "RC0603FR-075K1L") (field (name "PCB FOOTPRINT") "0603"))
      (libsource (lib "Full") (part "Res0.3"))
    )
    (comp (ref "R55")
      (value "5.1K")
      (footprint "res 0603")
      (description "RES SMD 5.1K OHM 1% 1/10W 0603")
      (fields (field (name "MANUFACTURER1_PART#") "RC0603FR-075K1L") (field (name "PCB FOOTPRINT") "0603"))
      (libsource (lib "Full") (part "Res0.3"))
    )
    (comp (ref "R56")
      (value "10K")
      (footprint "res 0603")
      (description "RES SMD,10K OHM 5% 1/10W 0603")
      (fields
        (field (name "MANUFACTURER1_PART#") "RMCF0603JT10K0")
        (field (name "MANUFACTURER2_PART#") "R0603J10KKDX")
        (field (name "PCB FOOTPRINT") "0603")
      )
      (libsource (lib "altium-import") (part "root_3_Res0.3_"))
    )
    (comp (ref "R57")
      (value "10K")
      (footprint "res 0603")
      (description "RES SMD,10K OHM 5% 1/10W 0603")
      (fields
        (field (name "MANUFACTURER1_PART#") "RMCF0603JT10K0")
        (field (name "MANUFACTURER2_PART#") "R0603J10KKDX")
        (field (name "PCB FOOTPRINT") "0603")
      )
      (libsource (lib "altium-import") (part "root_3_mirrored_Res0.3_"))
    )
    (comp (ref "R58")
      (value "5.1K")
      (footprint "res 0603")
      (description "RES SMD 5.1K OHM 1% 1/10W 0603")
      (fields (field (name "MANUFACTURER1_PART#") "RC0603FR-075K1L") (field (name "PCB FOOTPRINT") "0603"))
      (libsource (lib "Full") (part "Res0.3"))
    )
    (comp (ref "R59")
      (value "22R")
      (footprint "res 0603")
      (description "RES 22 OHM 5% 1/10W 0603")
      (fields
        (field (name "MANUFACTURER1_PART#") "RC0603JR-0722RL")
        (field (name "MANUFACTURER2_PART#") "RMCF0603JT22R0")
        (field (name "PCB FOOTPRINT") "0603")
      )
      (libsource (lib "Full") (part "Res0.3"))
    )
    (comp (ref "R60")
      (value "22R")
      (footprint "res 0603")
      (description "RES 22 OHM 5% 1/10W 0603")
      (fields
        (field (name "MANUFACTURER1_PART#") "RC0603JR-0722RL")
        (field (name "MANUFACTURER2_PART#") "RMCF0603JT22R0")
        (field (name "PCB FOOTPRINT") "0603")
      )
      (libsource (lib "Full") (part "Res0.3"))
    )
    (comp (ref "R61")
      (value "1K")
      (footprint "res 0603")
      (description "RES SMD,1K OHM,5%,1/10W,0603")
      (fields
        (field (name "MANUFACTURER1_PART#") "RMCF06031K00JNEAC")
        (field (name "MANUFACTURER2_PART#") "R0603J1KTG")
        (field (name "PCB FOOTPRINT") "0603")
        (field (name "POWER") "0.25W")
      )
      (libsource (lib "Full") (part "Res0.3"))
    )
    (comp (ref "R62")
      (value "10K")
      (footprint "res 0603")
      (description "RES SMD,10K OHM 5% 1/10W 0603")
      (fields
        (field (name "MANUFACTURER1_PART#") "RMCF0603JT10K0")
        (field (name "MANUFACTURER2_PART#") "R0603J10KKDX")
        (field (name "PCB FOOTPRINT") "0603")
      )
      (libsource (lib "altium-import") (part "root_3_mirrored_Res0.3_"))
    )
    (comp (ref "R63")
      (value "1K")
      (footprint "res 0603")
      (description "RES SMD,1K OHM,5%,1/10W,0603")
      (fields
        (field (name "MANUFACTURER1_PART#") "RMCF06031K00JNEAC")
        (field (name "MANUFACTURER2_PART#") "R0603J1KTG")
        (field (name "PCB FOOTPRINT") "0603")
        (field (name "POWER") "0.25W")
      )
      (libsource (lib "Full") (part "Res0.3"))
    )
    (comp (ref "R64")
      (value "10K")
      (footprint "res 0603")
      (description "RES SMD,10K OHM 5% 1/10W 0603")
      (fields
        (field (name "MANUFACTURER1_PART#") "RMCF0603JT10K0")
        (field (name "MANUFACTURER2_PART#") "R0603J10KKDX")
        (field (name "PCB FOOTPRINT") "0603")
        (field (name "ASSEMBLY") "NI")
      )
      (libsource (lib "altium-import") (part "root_3_mirrored_Res0.3_"))
    )
    (comp (ref "R65")
      (value "10K")
      (footprint "res 0603")
      (description "RES SMD,10K OHM 5% 1/10W 0603")
      (fields
        (field (name "MANUFACTURER1_PART#") "RMCF0603JT10K0")
        (field (name "MANUFACTURER2_PART#") "R0603J10KKDX")
        (field (name "PCB FOOTPRINT") "0603")
        (field (name "ASSEMBLY") "NI")
      )
      (libsource (lib "altium-import") (part "root_3_mirrored_Res0.3_"))
    )
    (comp (ref "R66")
      (value "1K")
      (footprint "res 0603")
      (description "RES SMD,1K OHM,5%,1/10W,0603")
      (fields
        (field (name "MANUFACTURER1_PART#") "RMCF06031K00JNEAC")
        (field (name "MANUFACTURER2_PART#") "R0603J1KTG")
        (field (name "PCB FOOTPRINT") "0603")
        (field (name "POWER") "0.25W")
      )
      (libsource (lib "Full") (part "Res0.3"))
    )
    (comp (ref "R67")
      (value "1K")
      (footprint "res 0603")
      (description "RES SMD,1K OHM,5%,1/10W,0603")
      (fields
        (field (name "MANUFACTURER1_PART#") "RMCF06031K00JNEAC")
        (field (name "MANUFACTURER2_PART#") "R0603J1KTG")
        (field (name "PCB FOOTPRINT") "0603")
        (field (name "POWER") "0.25W")
      )
      (libsource (lib "Full") (part "Res0.3"))
    )
    (comp (ref "R68")
      (value "1K")
      (footprint "res 0603")
      (description "RES SMD,1K OHM,5%,1/10W,0603")
      (fields
        (field (name "MANUFACTURER1_PART#") "RMCF06031K00JNEAC")
        (field (name "MANUFACTURER2_PART#") "R0603J1KTG")
        (field (name "PCB FOOTPRINT") "0603")
      )
      (libsource (lib "Full") (part "Res0.3"))
    )
    (comp (ref "R69")
      (value "1K")
      (footprint "res 0603")
      (description "RES SMD,1K OHM,5%,1/10W,0603")
      (fields
        (field (name "MANUFACTURER1_PART#") "RMCF06031K00JNEAC")
        (field (name "MANUFACTURER2_PART#") "R0603J1KTG")
        (field (name "PCB FOOTPRINT") "0603")
      )
      (libsource (lib "Full") (part "Res0.3"))
    )
    (comp (ref "R70")
      (value "10K")
      (footprint "res 0603")
      (description "RES SMD,10K OHM 5% 1/10W 0603")
      (fields
        (field (name "MANUFACTURER1_PART#") "RMCF0603JT10K0")
        (field (name "MANUFACTURER2_PART#") "R0603J10KKDX")
        (field (name "PCB FOOTPRINT") "0603")
      )
      (libsource (lib "altium-import") (part "root_2_mirrored_Res0.3_"))
    )
    (comp (ref "R71")
      (value "10K")
      (footprint "res 0603")
      (description "RES SMD,10K OHM 5% 1/10W 0603")
      (fields
        (field (name "MANUFACTURER1_PART#") "RMCF0603JT10K0")
        (field (name "MANUFACTURER2_PART#") "R0603J10KKDX")
        (field (name "PCB FOOTPRINT") "0603")
      )
      (libsource (lib "altium-import") (part "root_2_mirrored_Res0.3_"))
    )
    (comp (ref "R72")
      (value "10K")
      (footprint "res 0603")
      (description "RES SMD,10K OHM 5% 1/10W 0603")
      (fields
        (field (name "MANUFACTURER1_PART#") "RMCF0603JT10K0")
        (field (name "MANUFACTURER2_PART#") "R0603J10KKDX")
        (field (name "PCB FOOTPRINT") "0603")
        (field (name "ASSEMBLY") "NI")
      )
      (libsource (lib "altium-import") (part "root_3_mirrored_Res0.3_"))
    )
    (comp (ref "R73")
      (value "10K")
      (footprint "res 0603")
      (description "RES SMD,10K OHM 5% 1/10W 0603")
      (fields
        (field (name "MANUFACTURER1_PART#") "RMCF0603JT10K0")
        (field (name "MANUFACTURER2_PART#") "R0603J10KKDX")
        (field (name "PCB FOOTPRINT") "0603")
        (field (name "ASSEMBLY") "NI")
      )
      (libsource (lib "altium-import") (part "root_3_mirrored_Res0.3_"))
    )
    (comp (ref "R74")
      (value "1K")
      (footprint "res 0603")
      (description "RES SMD,1K OHM,5%,1/10W,0603")
      (fields
        (field (name "MANUFACTURER1_PART#") "RMCF06031K00JNEAC")
        (field (name "MANUFACTURER2_PART#") "R0603J1KTG")
        (field (name "PCB FOOTPRINT") "0603")
        (field (name "POWER") "0.25W")
      )
      (libsource (lib "Full") (part "Res0.3"))
    )
    (comp (ref "R75")
      (value "1K")
      (footprint "res 0603")
      (description "RES SMD,1K OHM,5%,1/10W,0603")
      (fields
        (field (name "MANUFACTURER1_PART#") "RMCF06031K00JNEAC")
        (field (name "MANUFACTURER2_PART#") "R0603J1KTG")
        (field (name "PCB FOOTPRINT") "0603")
        (field (name "POWER") "0.25W")
      )
      (libsource (lib "Full") (part "Res0.3"))
    )
    (comp (ref "R76")
      (value "1K")
      (footprint "res 0603")
      (description "RES SMD,1K OHM,5%,1/10W,0603")
      (fields
        (field (name "MANUFACTURER1_PART#") "RMCF06031K00JNEAC")
        (field (name "MANUFACTURER2_PART#") "R0603J1KTG")
        (field (name "PCB FOOTPRINT") "0603")
        (field (name "POWER") "0.25W")
      )
      (libsource (lib "Full") (part "Res0.3"))
    )
    (comp (ref "R77")
      (value "1K")
      (footprint "res 0603")
      (description "RES SMD,1K OHM,5%,1/10W,0603")
      (fields
        (field (name "MANUFACTURER1_PART#") "RMCF06031K00JNEAC")
        (field (name "MANUFACTURER2_PART#") "R0603J1KTG")
        (field (name "PCB FOOTPRINT") "0603")
        (field (name "POWER") "0.25W")
      )
      (libsource (lib "Full") (part "Res0.3"))
    )
    (comp (ref "R78")
      (value "1K")
      (footprint "res 0603")
      (description "RES SMD,1K OHM,5%,1/10W,0603")
      (fields
        (field (name "MANUFACTURER1_PART#") "RMCF06031K00JNEAC")
        (field (name "MANUFACTURER2_PART#") "R0603J1KTG")
        (field (name "PCB FOOTPRINT") "0603")
        (field (name "POWER") "0.25W")
      )
      (libsource (lib "Full") (part "Res0.3"))
    )
    (comp (ref "R79")
      (value "1K")
      (footprint "res 0603")
      (description "RES SMD,1K OHM,5%,1/10W,0603")
      (fields
        (field (name "MANUFACTURER1_PART#") "RMCF06031K00JNEAC")
        (field (name "MANUFACTURER2_PART#") "R0603J1KTG")
        (field (name "PCB FOOTPRINT") "0603")
      )
      (libsource (lib "Full") (part "Res0.3"))
    )
    (comp (ref "R80")
      (value "1K")
      (footprint "res 0603")
      (description "RES SMD,1K OHM,5%,1/10W,0603")
      (fields
        (field (name "MANUFACTURER1_PART#") "RMCF06031K00JNEAC")
        (field (name "MANUFACTURER2_PART#") "R0603J1KTG")
        (field (name "PCB FOOTPRINT") "0603")
      )
      (libsource (lib "Full") (part "Res0.3"))
    )
    (comp (ref "R81")
      (value "10K")
      (footprint "res 0603")
      (description "RES SMD,10K OHM 5% 1/10W 0603")
      (fields
        (field (name "MANUFACTURER1_PART#") "RMCF0603JT10K0")
        (field (name "MANUFACTURER2_PART#") "R0603J10KKDX")
        (field (name "PCB FOOTPRINT") "0603")
      )
      (libsource (lib "altium-import") (part "root_2_mirrored_Res0.3_"))
    )
    (comp (ref "R82")
      (value "10K")
      (footprint "res 0603")
      (description "RES SMD,10K OHM 5% 1/10W 0603")
      (fields
        (field (name "MANUFACTURER1_PART#") "RMCF0603JT10K0")
        (field (name "MANUFACTURER2_PART#") "R0603J10KKDX")
        (field (name "PCB FOOTPRINT") "0603")
      )
      (libsource (lib "altium-import") (part "root_2_mirrored_Res0.3_"))
    )
    (comp (ref "R83")
      (value "10K")
      (footprint "res 0603")
      (description "RES SMD,10K OHM 5% 1/10W 0603")
      (fields
        (field (name "MANUFACTURER1_PART#") "RMCF0603JT10K0")
        (field (name "MANUFACTURER2_PART#") "R0603J10KKDX")
        (field (name "PCB FOOTPRINT") "0603")
        (field (name "ASSEMBLY") "NI")
      )
      (libsource (lib "altium-import") (part "root_3_mirrored_Res0.3_"))
    )
    (comp (ref "R84")
      (value "1K")
      (footprint "res 0603")
      (description "RES SMD,1K OHM,5%,1/10W,0603")
      (fields
        (field (name "MANUFACTURER1_PART#") "RMCF06031K00JNEAC")
        (field (name "MANUFACTURER2_PART#") "R0603J1KTG")
        (field (name "PCB FOOTPRINT") "0603")
        (field (name "POWER") "0.25W")
      )
      (libsource (lib "Full") (part "Res0.3"))
    )
    (comp (ref "R85")
      (value "1K")
      (footprint "res 0603")
      (description "RES SMD,1K OHM,5%,1/10W,0603")
      (fields
        (field (name "MANUFACTURER1_PART#") "RMCF06031K00JNEAC")
        (field (name "MANUFACTURER2_PART#") "R0603J1KTG")
        (field (name "PCB FOOTPRINT") "0603")
      )
      (libsource (lib "Full") (part "Res0.3"))
    )
    (comp (ref "R86")
      (value "10K")
      (footprint "res 0603")
      (description "RES SMD,10K OHM 5% 1/10W 0603")
      (fields
        (field (name "MANUFACTURER1_PART#") "RMCF0603JT10K0")
        (field (name "MANUFACTURER2_PART#") "R0603J10KKDX")
        (field (name "PCB FOOTPRINT") "0603")
      )
      (libsource (lib "altium-import") (part "root_2_mirrored_Res0.3_"))
    )
    (comp (ref "R87")
      (value "1K")
      (footprint "res 0603")
      (description "RES SMD,1K OHM,5%,1/10W,0603")
      (fields
        (field (name "MANUFACTURER1_PART#") "RMCF06031K00JNEAC")
        (field (name "MANUFACTURER2_PART#") "R0603J1KTG")
        (field (name "PCB FOOTPRINT") "0603")
        (field (name "POWER") "0.25W")
      )
      (libsource (lib "Full") (part "Res0.3"))
    )
    (comp (ref "R88")
      (value "1K")
      (footprint "res 0603")
      (description "RES SMD,1K OHM,5%,1/10W,0603")
      (fields
        (field (name "MANUFACTURER1_PART#") "RMCF06031K00JNEAC")
        (field (name "MANUFACTURER2_PART#") "R0603J1KTG")
        (field (name "PCB FOOTPRINT") "0603")
        (field (name "POWER") "0.25W")
      )
      (libsource (lib "Full") (part "Res0.3"))
    )
    (comp (ref "R89")
      (value "1K")
      (footprint "res 0603")
      (description "RES SMD,1K OHM,5%,1/10W,0603")
      (fields
        (field (name "MANUFACTURER1_PART#") "RMCF06031K00JNEAC")
        (field (name "MANUFACTURER2_PART#") "R0603J1KTG")
        (field (name "PCB FOOTPRINT") "0603")
        (field (name "POWER") "0.25W")
      )
      (libsource (lib "Full") (part "Res0.3"))
    )
    (comp (ref "R119")
      (value "10K")
      (footprint "res 0603")
      (description "RES SMD,10K OHM 5% 1/10W 0603")
      (fields
        (field (name "MANUFACTURER1_PART#") "RMCF0603JT10K0")
        (field (name "MANUFACTURER2_PART#") "R0603J10KKDX")
        (field (name "PCB FOOTPRINT") "0603")
      )
      (libsource (lib "altium-import") (part "root_0_Res0.3_"))
    )
    (comp (ref "R120")
      (value "1K")
      (footprint "res 0603")
      (description "RES SMD,1K OHM,5%,1/10W,0603")
      (fields
        (field (name "MANUFACTURER1_PART#") "RMCF06031K00JNEAC")
        (field (name "MANUFACTURER2_PART#") "R0603J1KTG")
        (field (name "PCB FOOTPRINT") "0603")
      )
      (libsource (lib "Full") (part "Res0.3"))
    )
    (comp (ref "R121")
      (value "470R")
      (footprint "res 0603")
      (description "RES SMD, 470 OHM 5% 1/8W 0603")
      (fields
        (field (name "MANUFACTURER1_PART#") "RK73B1JTTD471J")
        (field (name "MANUFACTURER2_PART#") "RMCF0603JT470R")
      )
      (libsource (lib "Full") (part "Res0.3"))
    )
    (comp (ref "R122")
      (value "1K")
      (footprint "res 0603")
      (description "RES SMD,1K OHM,5%,1/10W,0603")
      (fields
        (field (name "MANUFACTURER1_PART#") "RMCF06031K00JNEAC")
        (field (name "MANUFACTURER2_PART#") "R0603J1KTG")
        (field (name "PCB FOOTPRINT") "0603")
      )
      (libsource (lib "Full") (part "Res0.3"))
    )
    (comp (ref "R123")
      (value "1K")
      (footprint "res 0603")
      (description "RES SMD,1K OHM,5%,1/10W,0603")
      (fields
        (field (name "MANUFACTURER1_PART#") "RMCF06031K00JNEAC")
        (field (name "MANUFACTURER2_PART#") "R0603J1KTG")
        (field (name "PCB FOOTPRINT") "0603")
      )
      (libsource (lib "Full") (part "Res0.3"))
    )
    (comp (ref "R124")
      (value "10K")
      (footprint "res 0603")
      (description "RES SMD,10K OHM 5% 1/10W 0603")
      (fields
        (field (name "MANUFACTURER1_PART#") "RMCF0603JT10K0")
        (field (name "MANUFACTURER2_PART#") "R0603J10KKDX")
        (field (name "PCB FOOTPRINT") "0603")
      )
      (libsource (lib "altium-import") (part "root_0_Res0.3_"))
    )
    (comp (ref "R125")
      (value "470R")
      (footprint "res 0603")
      (description "RES SMD, 470 OHM 5% 1/8W 0603")
      (fields
        (field (name "MANUFACTURER1_PART#") "RK73B1JTTD471J")
        (field (name "MANUFACTURER2_PART#") "RMCF0603JT470R")
      )
      (libsource (lib "Full") (part "Res0.3"))
    )
    (comp (ref "R126")
      (value "1K")
      (footprint "res 0603")
      (description "RES SMD,1K OHM,5%,1/10W,0603")
      (fields
        (field (name "MANUFACTURER1_PART#") "RMCF06031K00JNEAC")
        (field (name "MANUFACTURER2_PART#") "R0603J1KTG")
        (field (name "PCB FOOTPRINT") "0603")
      )
      (libsource (lib "Full") (part "Res0.3"))
    )
    (comp (ref "R127")
      (value "0.05R")
      (footprint "res 2512")
      (description "RES SMD 0.05 OHM 1% 1W 2512")
      (fields
        (field (name "MANUFACTURER1_PART#") "TLRP3A30CR050FTE")
        (field (name "MANUFACTURER2_PART#") "https://banlinhkien.com/tro-2512-1-r0500.05r-1w-p6652906.html")
        (field (name "PCB FOOTPRINT") "2512")
      )
      (libsource (lib "Full") (part "Res0.3"))
    )
    (comp (ref "R128")
      (value "0.05R")
      (footprint "res 2512")
      (description "RES SMD 0.05 OHM 1% 1W 2512")
      (fields
        (field (name "MANUFACTURER1_PART#") "TLRP3A30CR050FTE")
        (field (name "MANUFACTURER2_PART#") "https://banlinhkien.com/tro-2512-1-r0500.05r-1w-p6652906.html")
        (field (name "PCB FOOTPRINT") "2512")
      )
      (libsource (lib "Full") (part "Res0.3"))
    )
    (comp (ref "U4")
      (value "TPS54302DDCR")
      (footprint "SOT23-6")
      (description "IC REG BUCK ADJ 3A TSOT23-6,TPS54302DDCR")
      (fields
        (field (name "DISTR1_PART#") "296-46237-1-ND")
        (field (name "PACKAGE") "TSOT23-6")
        (field (name "BY") "VINFAST_RD")
      )
      (libsource (lib "*") (part "IC_TPS54302DDCR"))
    )
    (comp (ref "U8")
      (value "LM358BIDGKR")
      (footprint "SOIC-8")
      (description "IC OPAMP GP 2 CIRCUIT 8SOIC")
      (fields
        (field (name "MANUFACTURER2_PART#") "LM358DR2G")
        (field (name "MANUFACTURER1_PART#") "LM358BAIDR")
      )
      (libsource (lib "VSM") (part "LM358"))
    )
    (comp (ref "Z1")
      (value "MMSZ4683T1G")
      (footprint "Hiendv:SOD3716X135N")
      (description "DIODE ZENER 3V 500MW SOD123")
      (fields (field (name "MOUSER PART NUMBER") "863-MMSZ4683T1G"))
      (libsource (lib "*") (part "MMSZ4683T1G"))
    )
    (comp (ref "Z2")
      (value "MMSZ4683T1G")
      (footprint "Hiendv:SOD3716X135N")
      (description "DIODE ZENER 3V 500MW SOD123")
      (fields (field (name "MOUSER PART NUMBER") "863-MMSZ4683T1G"))
      (libsource (lib "*") (part "MMSZ4683T1G"))
    )
    (comp (ref "Z3")
      (value "MMSZ4683T1G")
      (footprint "Hiendv:SOD3716X135N")
      (description "DIODE ZENER 3V 500MW SOD123")
      (fields (field (name "MOUSER PART NUMBER") "863-MMSZ4683T1G"))
      (libsource (lib "*") (part "MMSZ4683T1G"))
    )
    (comp (ref "Z4")
      (value "MMSZ4683T1G")
      (footprint "Hiendv:SOD3716X135N")
      (description "DIODE ZENER 3V 500MW SOD123")
      (fields (field (name "MOUSER PART NUMBER") "863-MMSZ4683T1G"))
      (libsource (lib "*") (part "MMSZ4683T1G"))
    )
    (comp (ref "Z5")
      (value "MMSZ4683T1G")
      (footprint "Hiendv:SOD3716X135N")
      (description "DIODE ZENER 3V 500MW SOD123")
      (fields (field (name "MOUSER PART NUMBER") "863-MMSZ4683T1G"))
      (libsource (lib "*") (part "MMSZ4683T1G"))
    )
    (comp (ref "Z6")
      (value "MMSZ4683T1G")
      (footprint "Hiendv:SOD3716X135N")
      (description "DIODE ZENER 3V 500MW SOD123")
      (fields (field (name "MOUSER PART NUMBER") "863-MMSZ4683T1G"))
      (libsource (lib "*") (part "MMSZ4683T1G"))
    )
    (comp (ref "Z7")
      (value "MMSZ4683T1G")
      (footprint "Hiendv:SOD3716X135N")
      (description "DIODE ZENER 3V 500MW SOD123")
      (fields (field (name "MOUSER PART NUMBER") "863-MMSZ4683T1G"))
      (libsource (lib "*") (part "MMSZ4683T1G"))
    )
    (comp (ref "Z8")
      (value "MMSZ4683T1G")
      (footprint "Hiendv:SOD3716X135N")
      (description "DIODE ZENER 3V 500MW SOD123")
      (fields (field (name "MOUSER PART NUMBER") "863-MMSZ4683T1G"))
      (libsource (lib "*") (part "MMSZ4683T1G"))
    )
  )
  (nets
    (net (code "1") (name "+24V_SYS") (class "Default")
      (node (ref "D13") (pin "2") (pinfunction "K_2") (pintype "passive"))
      (node (ref "D14") (pin "2") (pinfunction "K_2") (pintype "passive"))
      (node (ref "D15") (pin "2") (pinfunction "K_2") (pintype "passive"))
      (node (ref "D19") (pin "2") (pinfunction "K_2") (pintype "passive"))
      (node (ref "D20") (pin "2") (pinfunction "K_2") (pintype "passive"))
      (node (ref "D21") (pin "2") (pinfunction "K_2") (pintype "passive"))
      (node (ref "K1") (pin "2") (pinfunction "COIL_1_2") (pintype "passive"))
      (node (ref "K2") (pin "2") (pinfunction "COIL_1_2") (pintype "passive"))
      (node (ref "K3") (pin "2") (pinfunction "COIL_1_2") (pintype "passive"))
      (node (ref "K4") (pin "2") (pinfunction "COIL_1_2") (pintype "passive"))
      (node (ref "K5") (pin "2") (pinfunction "COIL_1_2") (pintype "passive"))
      (node (ref "K6") (pin "2") (pinfunction "COIL_1_2") (pintype "passive"))
      (node (ref "L5") (pin "1") (pinfunction "1_1") (pintype "passive"))
      (node (ref "P10") (pin "3") (pinfunction "3_3") (pintype "passive"))
      (node (ref "P2") (pin "4") (pinfunction "4_4") (pintype "passive"))
      (node (ref "P3") (pin "1") (pinfunction "1_1") (pintype "passive"))
      (node (ref "P3") (pin "2") (pinfunction "2_2") (pintype "passive"))
      (node (ref "P3") (pin "3") (pinfunction "3_3") (pintype "passive"))
      (node (ref "P7") (pin "3") (pinfunction "3_3") (pintype "passive"))
      (node (ref "Q11") (pin "3") (pinfunction "S_3") (pintype "passive"))
      (node (ref "Q5") (pin "3") (pinfunction "S_3") (pintype "passive"))
      (node (ref "Q8") (pin "3") (pinfunction "S_3") (pintype "passive"))
      (node (ref "R45") (pin "1") (pinfunction "1_1") (pintype "passive"))
      (node (ref "R57") (pin "1") (pinfunction "1_1") (pintype "passive"))
      (node (ref "R62") (pin "1") (pinfunction "1_1") (pintype "passive"))
    )
    (net (code "2") (name "/COL1") (class "Default")
      (node (ref "P1") (pin "1") (pinfunction "1_1") (pintype "passive"))
      (node (ref "R29") (pin "2") (pinfunction "2_2") (pintype "passive"))
    )
    (net (code "3") (name "/COL2") (class "Default")
      (node (ref "P1") (pin "3") (pinfunction "3_3") (pintype "passive"))
      (node (ref "R32") (pin "2") (pinfunction "2_2") (pintype "passive"))
    )
    (net (code "4") (name "/COL3") (class "Default")
      (node (ref "P1") (pin "5") (pinfunction "5_5") (pintype "passive"))
      (node (ref "R33") (pin "2") (pinfunction "2_2") (pintype "passive"))
    )
    (net (code "5") (name "/COL4") (class "Default")
      (node (ref "P1") (pin "7") (pinfunction "7_7") (pintype "passive"))
      (node (ref "R34") (pin "2") (pinfunction "2_2") (pintype "passive"))
    )
    (net (code "6") (name "/Conveyer_motor") (class "Default")
      (node (ref "R50") (pin "2") (pinfunction "2_2") (pintype "passive"))
    )
    (net (code "7") (name "/DHT21") (class "Default")
      (node (ref "J7") (pin "2") (pinfunction "2_2") (pintype "passive"))
      (node (ref "R15") (pin "1") (pinfunction "1_1") (pintype "passive"))
    )
    (net (code "8") (name "/DOOR") (class "Default")
      (node (ref "D3") (pin "2") (pinfunction "K_2") (pintype "passive"))
      (node (ref "P2") (pin "1") (pinfunction "1_1") (pintype "passive"))
      (node (ref "R11") (pin "1") (pinfunction "1_1") (pintype "passive"))
    )
    (net (code "9") (name "/DROP") (class "Default")
      (node (ref "D6") (pin "2") (pinfunction "K_2") (pintype "passive"))
      (node (ref "P10") (pin "4") (pinfunction "4_4") (pintype "passive"))
      (node (ref "R23") (pin "1") (pinfunction "1_1") (pintype "passive"))
    )
    (net (code "10") (name "/EMPTY") (class "Default")
      (node (ref "D7") (pin "2") (pinfunction "K_2") (pintype "passive"))
      (node (ref "P7") (pin "4") (pinfunction "4_4") (pintype "passive"))
      (node (ref "R31") (pin "1") (pinfunction "1_1") (pintype "passive"))
    )
    (net (code "11") (name "/GND_SWap_motor") (class "Default")
      (node (ref "C86") (pin "1") (pinfunction "1_1") (pintype "passive"))
      (node (ref "D26") (pin "1") (pinfunction "A_1") (pintype "passive"))
      (node (ref "P7") (pin "5") (pinfunction "5_5") (pintype "passive"))
      (node (ref "R126") (pin "2") (pinfunction "2_2") (pintype "passive"))
      (node (ref "R128") (pin "1") (pinfunction "1_1") (pintype "passive"))
    )
    (net (code "12") (name "/GND_motor") (class "Default")
      (node (ref "C85") (pin "1") (pinfunction "1_1") (pintype "passive"))
      (node (ref "D25") (pin "1") (pinfunction "A_1") (pintype "passive"))
      (node (ref "P10") (pin "5") (pinfunction "5_5") (pintype "passive"))
      (node (ref "R122") (pin "2") (pinfunction "2_2") (pintype "passive"))
      (node (ref "R127") (pin "1") (pinfunction "1_1") (pintype "passive"))
    )
    (net (code "13") (name "/Heater") (class "Default")
      (node (ref "R76") (pin "2") (pinfunction "2_2") (pintype "passive"))
    )
    (net (code "14") (name "/Heater1") (class "Default")
      (node (ref "K1") (pin "3") (pinfunction "NO_3") (pintype "passive"))
      (node (ref "P9") (pin "2") (pinfunction "2_2") (pintype "passive"))
    )
    (net (code "15") (name "/Heater2") (class "Default")
      (node (ref "K1") (pin "1") (pinfunction "COM_1") (pintype "passive"))
      (node (ref "P9") (pin "1") (pinfunction "1_1") (pintype "passive"))
    )
    (net (code "16") (name "/INPUT1") (class "Default")
      (node (ref "D11") (pin "2") (pinfunction "K_2") (pintype "passive"))
      (node (ref "J4") (pin "2") (pinfunction "2_2") (pintype "passive"))
      (node (ref "R70") (pin "1") (pinfunction "1_1") (pintype "passive"))
    )
    (net (code "17") (name "/INPUT2") (class "Default")
      (node (ref "D16") (pin "2") (pinfunction "K_2") (pintype "passive"))
      (node (ref "J4") (pin "3") (pinfunction "3_3") (pintype "passive"))
      (node (ref "R81") (pin "1") (pinfunction "1_1") (pintype "passive"))
    )
    (net (code "18") (name "/INPUT3") (class "Default")
      (node (ref "D18") (pin "2") (pinfunction "K_2") (pintype "passive"))
      (node (ref "J4") (pin "4") (pinfunction "4_4") (pintype "passive"))
      (node (ref "R86") (pin "1") (pinfunction "1_1") (pintype "passive"))
    )
    (net (code "19") (name "/INPUT4") (class "Default")
      (node (ref "D12") (pin "2") (pinfunction "K_2") (pintype "passive"))
      (node (ref "J4") (pin "5") (pinfunction "5_5") (pintype "passive"))
      (node (ref "R71") (pin "1") (pinfunction "1_1") (pintype "passive"))
    )
    (net (code "20") (name "/INPUT5") (class "Default")
      (node (ref "D17") (pin "2") (pinfunction "K_2") (pintype "passive"))
      (node (ref "J4") (pin "6") (pinfunction "6_6") (pintype "passive"))
      (node (ref "R82") (pin "1") (pinfunction "1_1") (pintype "passive"))
    )
    (net (code "21") (name "/IN_DOOR") (class "Default")
      (node (ref "C25") (pin "2") (pinfunction "2_2") (pintype "passive"))
      (node (ref "R8") (pin "1") (pinfunction "1_1") (pintype "passive"))
      (node (ref "Z1") (pin "1") (pinfunction "K_1") (pintype "passive"))
    )
    (net (code "22") (name "/IN_DROP") (class "Default")
      (node (ref "C26") (pin "2") (pinfunction "2_2") (pintype "passive"))
      (node (ref "R20") (pin "1") (pinfunction "1_1") (pintype "passive"))
      (node (ref "Z2") (pin "1") (pinfunction "K_1") (pintype "passive"))
    )
    (net (code "23") (name "/IN_EMPTY") (class "Default")
      (node (ref "C27") (pin "2") (pinfunction "2_2") (pintype "passive"))
      (node (ref "R28") (pin "1") (pinfunction "1_1") (pintype "passive"))
      (node (ref "Z3") (pin "1") (pinfunction "K_1") (pintype "passive"))
    )
    (net (code "24") (name "/I_M_SENSE") (class "Default")
      (node (ref "C81") (pin "1") (pinfunction "1_1") (pintype "passive"))
      (node (ref "R119") (pin "2") (pinfunction "2_2") (pintype "passive"))
      (node (ref "R121") (pin "1") (pinfunction "1_1") (pintype "passive"))
      (node (ref "U8") (pin "1") (pinfunction "OUT_1") (pintype "passive"))
    )
    (net (code "25") (name "/KP_COL1") (class "Default")
      (node (ref "R29") (pin "1") (pinfunction "1_1") (pintype "passive"))
    )
    (net (code "26") (name "/KP_COL2") (class "Default")
      (node (ref "R32") (pin "1") (pinfunction "1_1") (pintype "passive"))
    )
    (net (code "27") (name "/KP_COL3") (class "Default")
      (node (ref "R33") (pin "1") (pinfunction "1_1") (pintype "passive"))
    )
    (net (code "28") (name "/KP_COL4") (class "Default")
      (node (ref "R34") (pin "1") (pinfunction "1_1") (pintype "passive"))
    )
    (net (code "29") (name "/KP_ROW1") (class "Default")
      (node (ref "R35") (pin "1") (pinfunction "1_1") (pintype "passive"))
    )
    (net (code "30") (name "/KP_ROW2") (class "Default")
      (node (ref "R36") (pin "1") (pinfunction "1_1") (pintype "passive"))
    )
    (net (code "31") (name "/KP_ROW3") (class "Default")
      (node (ref "R37") (pin "1") (pinfunction "1_1") (pintype "passive"))
    )
    (net (code "32") (name "/KP_ROW4") (class "Default")
      (node (ref "R38") (pin "1") (pinfunction "1_1") (pintype "passive"))
    )
    (net (code "33") (name "/LCD_CLK") (class "Default")
      (node (ref "HD1") (pin "6") (pinfunction "6_6") (pintype "passive"))
      (node (ref "R12") (pin "2") (pinfunction "2_2") (pintype "passive"))
    )
    (net (code "34") (name "/LCD_CS") (class "Default")
      (node (ref "HD1") (pin "4") (pinfunction "4_4") (pintype "passive"))
      (node (ref "R7") (pin "2") (pinfunction "2_2") (pintype "passive"))
    )
    (net (code "35") (name "/LCD_DI") (class "Default")
      (node (ref "HD1") (pin "5") (pinfunction "5_5") (pintype "passive"))
      (node (ref "R9") (pin "2") (pinfunction "2_2") (pintype "passive"))
    )
    (net (code "36") (name "/LCD_DO") (class "Default")
      (node (ref "HD1") (pin "8") (pinfunction "8_8") (pintype "passive"))
      (node (ref "R16") (pin "2") (pinfunction "2_2") (pintype "passive"))
    )
    (net (code "37") (name "/LCD_INT") (class "Default")
      (node (ref "HD1") (pin "7") (pinfunction "7_7") (pintype "passive"))
      (node (ref "R14") (pin "2") (pinfunction "2_2") (pintype "passive"))
    )
    (net (code "38") (name "/LCD_KLIGHT") (class "Default")
      (node (ref "HD1") (pin "20") (pinfunction "20_20") (pintype "passive"))
      (node (ref "R19") (pin "1") (pinfunction "1_1") (pintype "passive"))
    )
    (net (code "39") (name "/LCD_RST") (class "Default")
      (node (ref "HD1") (pin "17") (pinfunction "17_17") (pintype "passive"))
      (node (ref "R13") (pin "2") (pinfunction "2_2") (pintype "passive"))
    )
    (net (code "40") (name "/LCD_VDD") (class "Default")
      (node (ref "C24") (pin "2") (pinfunction "2_2") (pintype "passive"))
      (node (ref "HD1") (pin "19") (pinfunction "19_19") (pintype "passive"))
      (node (ref "HD1") (pin "2") (pinfunction "2_2") (pintype "passive"))
      (node (ref "L3") (pin "2") (pinfunction "2_2") (pintype "passive"))
    )
    (net (code "41") (name "/LED_1") (class "Default")
      (node (ref "R43") (pin "2") (pinfunction "2_2") (pintype "passive"))
    )
    (net (code "42") (name "/LED_2") (class "Default")
      (node (ref "R42") (pin "2") (pinfunction "2_2") (pintype "passive"))
    )
    (net (code "43") (name "/LED_3") (class "Default")
      (node (ref "R44") (pin "2") (pinfunction "2_2") (pintype "passive"))
    )
    (net (code "44") (name "/MCU_IN1") (class "Default")
      (node (ref "C41") (pin "2") (pinfunction "2_2") (pintype "passive"))
      (node (ref "R66") (pin "1") (pinfunction "1_1") (pintype "passive"))
      (node (ref "Z4") (pin "1") (pinfunction "K_1") (pintype "passive"))
    )
    (net (code "45") (name "/MCU_IN2") (class "Default")
      (node (ref "C43") (pin "2") (pinfunction "2_2") (pintype "passive"))
      (node (ref "R74") (pin "1") (pinfunction "1_1") (pintype "passive"))
      (node (ref "Z6") (pin "1") (pinfunction "K_1") (pintype "passive"))
    )
    (net (code "46") (name "/MCU_IN3") (class "Default")
      (node (ref "C45") (pin "2") (pinfunction "2_2") (pintype "passive"))
      (node (ref "R84") (pin "1") (pinfunction "1_1") (pintype "passive"))
      (node (ref "Z8") (pin "1") (pinfunction "K_1") (pintype "passive"))
    )
    (net (code "47") (name "/MCU_IN4") (class "Default")
      (node (ref "C42") (pin "2") (pinfunction "2_2") (pintype "passive"))
      (node (ref "R67") (pin "1") (pinfunction "1_1") (pintype "passive"))
      (node (ref "Z5") (pin "1") (pinfunction "K_1") (pintype "passive"))
    )
    (net (code "48") (name "/MCU_IN5") (class "Default")
      (node (ref "C44") (pin "2") (pinfunction "2_2") (pintype "passive"))
      (node (ref "R75") (pin "1") (pinfunction "1_1") (pintype "passive"))
      (node (ref "Z7") (pin "1") (pinfunction "K_1") (pintype "passive"))
    )
    (net (code "49") (name "/MCU_LCD_CLK") (class "Default")
      (node (ref "R12") (pin "1") (pinfunction "1_1") (pintype "passive"))
    )
    (net (code "50") (name "/MCU_LCD_CS") (class "Default")
      (node (ref "R7") (pin "1") (pinfunction "1_1") (pintype "passive"))
    )
    (net (code "51") (name "/MCU_LCD_DATA") (class "Default")
      (node (ref "R9") (pin "1") (pinfunction "1_1") (pintype "passive"))
    )
    (net (code "52") (name "/MCU_LCD_DO") (class "Default")
      (node (ref "R16") (pin "1") (pinfunction "1_1") (pintype "passive"))
    )
    (net (code "53") (name "/MCU_LCD_INT") (class "Default")
      (node (ref "R14") (pin "1") (pinfunction "1_1") (pintype "passive"))
    )
    (net (code "54") (name "/MCU_LCD_LIGHT") (class "Default")
      (node (ref "R25") (pin "2") (pinfunction "2_2") (pintype "passive"))
    )
    (net (code "55") (name "/MCU_LCD_RST") (class "Default")
      (node (ref "R13") (pin "1") (pinfunction "1_1") (pintype "passive"))
    )
    (net (code "56") (name "/MCU_MOTOR_CUR") (class "Default")
      (node (ref "C82") (pin "2") (pinfunction "2_2") (pintype "passive"))
      (node (ref "R121") (pin "2") (pinfunction "2_2") (pintype "passive"))
    )
    (net (code "57") (name "/MCU_MOTOR_SWAP_CUR_ADC") (class "Default")
      (node (ref "C84") (pin "2") (pinfunction "2_2") (pintype "passive"))
      (node (ref "R125") (pin "1") (pinfunction "1_1") (pintype "passive"))
    )
    (net (code "58") (name "/MCU_RELAY1") (class "Default")
      (node (ref "R87") (pin "2") (pinfunction "2_2") (pintype "passive"))
    )
    (net (code "59") (name "/MCU_RELAY2") (class "Default")
      (node (ref "R77") (pin "2") (pinfunction "2_2") (pintype "passive"))
    )
    (net (code "60") (name "/MCU_RELAY3") (class "Default")
      (node (ref "R88") (pin "2") (pinfunction "2_2") (pintype "passive"))
    )
    (net (code "61") (name "/MCU_RELAY4") (class "Default")
      (node (ref "R78") (pin "2") (pinfunction "2_2") (pintype "passive"))
    )
    (net (code "62") (name "/MCU_RELAY5") (class "Default")
      (node (ref "R89") (pin "2") (pinfunction "2_2") (pintype "passive"))
    )
    (net (code "63") (name "/MCU_RX_VADI") (class "Default")
      (node (ref "Q7") (pin "3") (pinfunction "C_3") (pintype "passive"))
      (node (ref "R55") (pin "2") (pinfunction "2_2") (pintype "passive"))
    )
    (net (code "64") (name "/MCU_TX_VADI") (class "Default")
      (node (ref "Q10") (pin "2") (pinfunction "E_2") (pintype "passive"))
    )
    (net (code "65") (name "/RELAY1_1") (class "Default")
      (node (ref "K4") (pin "3") (pinfunction "NO_3") (pintype "passive"))
      (node (ref "P8") (pin "6") (pinfunction "6_6") (pintype "passive"))
    )
    (net (code "66") (name "/RELAY1_2") (class "Default")
      (node (ref "K4") (pin "1") (pinfunction "COM_1") (pintype "passive"))
      (node (ref "P8") (pin "1") (pinfunction "1_1") (pintype "passive"))
    )
    (net (code "67") (name "/RELAY2_1") (class "Default")
      (node (ref "K2") (pin "3") (pinfunction "NO_3") (pintype "passive"))
      (node (ref "P8") (pin "7") (pinfunction "7_7") (pintype "passive"))
    )
    (net (code "68") (name "/RELAY2_2") (class "Default")
      (node (ref "K2") (pin "1") (pinfunction "COM_1") (pintype "passive"))
      (node (ref "P8") (pin "2") (pinfunction "2_2") (pintype "passive"))
    )
    (net (code "69") (name "/RELAY3_1") (class "Default")
      (node (ref "K5") (pin "3") (pinfunction "NO_3") (pintype "passive"))
      (node (ref "P8") (pin "8") (pinfunction "8_8") (pintype "passive"))
    )
    (net (code "70") (name "/RELAY3_2") (class "Default")
      (node (ref "K5") (pin "1") (pinfunction "COM_1") (pintype "passive"))
      (node (ref "P8") (pin "3") (pinfunction "3_3") (pintype "passive"))
    )
    (net (code "71") (name "/RELAY4_1") (class "Default")
      (node (ref "K3") (pin "3") (pinfunction "NO_3") (pintype "passive"))
      (node (ref "P8") (pin "9") (pinfunction "9_9") (pintype "passive"))
    )
    (net (code "72") (name "/RELAY4_2") (class "Default")
      (node (ref "K3") (pin "1") (pinfunction "COM_1") (pintype "passive"))
      (node (ref "P8") (pin "4") (pinfunction "4_4") (pintype "passive"))
    )
    (net (code "73") (name "/RELAY5_1") (class "Default")
      (node (ref "K6") (pin "3") (pinfunction "NO_3") (pintype "passive"))
      (node (ref "P8") (pin "10") (pinfunction "10_10") (pintype "passive"))
    )
    (net (code "74") (name "/RELAY5_2") (class "Default")
      (node (ref "K6") (pin "1") (pinfunction "COM_1") (pintype "passive"))
      (node (ref "P8") (pin "5") (pinfunction "5_5") (pintype "passive"))
    )
    (net (code "75") (name "/ROW1") (class "Default")
      (node (ref "C31") (pin "2") (pinfunction "2_2") (pintype "passive"))
      (node (ref "P1") (pin "2") (pinfunction "2_2") (pintype "passive"))
      (node (ref "R35") (pin "2") (pinfunction "2_2") (pintype "passive"))
    )
    (net (code "76") (name "/ROW2") (class "Default")
      (node (ref "C30") (pin "2") (pinfunction "2_2") (pintype "passive"))
      (node (ref "P1") (pin "4") (pinfunction "4_4") (pintype "passive"))
      (node (ref "R36") (pin "2") (pinfunction "2_2") (pintype "passive"))
    )
    (net (code "77") (name "/ROW3") (class "Default")
      (node (ref "C29") (pin "2") (pinfunction "2_2") (pintype "passive"))
      (node (ref "P1") (pin "6") (pinfunction "6_6") (pintype "passive"))
      (node (ref "R37") (pin "2") (pinfunction "2_2") (pintype "passive"))
    )
    (net (code "78") (name "/ROW4") (class "Default")
      (node (ref "C28") (pin "2") (pinfunction "2_2") (pintype "passive"))
      (node (ref "P1") (pin "8") (pinfunction "8_8") (pintype "passive"))
      (node (ref "R38") (pin "2") (pinfunction "2_2") (pintype "passive"))
    )
    (net (code "79") (name "/Solenoid") (class "Default")
      (node (ref "R63") (pin "2") (pinfunction "2_2") (pintype "passive"))
    )
    (net (code "80") (name "/Solenoid_out") (class "Default")
      (node (ref "D10") (pin "2") (pinfunction "K_2") (pintype "passive"))
      (node (ref "P10") (pin "1") (pinfunction "1_1") (pintype "passive"))
      (node (ref "Q11") (pin "2") (pinfunction "D_2") (pintype "passive"))
    )
    (net (code "81") (name "/Swap_motor") (class "Default")
      (node (ref "R61") (pin "2") (pinfunction "2_2") (pintype "passive"))
    )
    (net (code "82") (name "/VADI_RX") (class "Default")
      (node (ref "D9") (pin "1") (pinfunction "K_1") (pintype "passive"))
      (node (ref "P4") (pin "4") (pinfunction "4_4") (pintype "passive"))
      (node (ref "R60") (pin "2") (pinfunction "2_2") (pintype "passive"))
    )
    (net (code "83") (name "/VADI_TX") (class "Default")
      (node (ref "D9") (pin "2") (pinfunction "K_2") (pintype "passive"))
      (node (ref "P4") (pin "5") (pinfunction "5_5") (pintype "passive"))
      (node (ref "R59") (pin "2") (pinfunction "2_2") (pintype "passive"))
    )
    (net (code "84") (name "/V_SWap_motor") (class "Default")
      (node (ref "D8") (pin "2") (pinfunction "K_2") (pintype "passive"))
      (node (ref "P7") (pin "2") (pinfunction "2_2") (pintype "passive"))
      (node (ref "Q8") (pin "2") (pinfunction "D_2") (pintype "passive"))
    )
    (net (code "85") (name "3V3") (class "Default")
      (node (ref "C40") (pin "2") (pinfunction "2_2") (pintype "passive"))
      (node (ref "F2") (pin "1") (pinfunction "1_1") (pintype "passive"))
      (node (ref "J7") (pin "3") (pinfunction "3_3") (pintype "passive"))
      (node (ref "R15") (pin "2") (pinfunction "2_2") (pintype "passive"))
      (node (ref "R18") (pin "1") (pinfunction "1_1") (pintype "passive"))
      (node (ref "R27") (pin "1") (pinfunction "1_1") (pintype "passive"))
      (node (ref "R55") (pin "1") (pinfunction "1_1") (pintype "passive"))
      (node (ref "R56") (pin "1") (pinfunction "1_1") (pintype "passive"))
      (node (ref "R6") (pin "1") (pinfunction "1_1") (pintype "passive"))
      (node (ref "R64") (pin "1") (pinfunction "1_1") (pintype "passive"))
      (node (ref "R65") (pin "1") (pinfunction "1_1") (pintype "passive"))
      (node (ref "R72") (pin "1") (pinfunction "1_1") (pintype "passive"))
      (node (ref "R73") (pin "1") (pinfunction "1_1") (pintype "passive"))
      (node (ref "R83") (pin "1") (pinfunction "1_1") (pintype "passive"))
    )
    (net (code "86") (name "5V") (class "Default")
      (node (ref "C39") (pin "1") (pinfunction "1_1") (pintype "passive"))
      (node (ref "R52") (pin "1") (pinfunction "1_1") (pintype "passive"))
      (node (ref "R54") (pin "1") (pinfunction "1_1") (pintype "passive"))
      (node (ref "R58") (pin "1") (pinfunction "1_1") (pintype "passive"))
    )
    (net (code "87") (name "5V0") (class "Default")
      (node (ref "L3") (pin "1") (pinfunction "1_1") (pintype "passive"))
    )
    (net (code "88") (name "5V_OUT") (class "Default")
      (node (ref "U8") (pin "8") (pinfunction "+V_8") (pintype "passive"))
    )
    (net (code "89") (name "12V_VADI") (class "Default")
      (node (ref "P4") (pin "3") (pinfunction "3_3") (pintype "passive"))
    )
    (net (code "90") (name "DGND") (class "Default")
      (node (ref "C24") (pin "1") (pinfunction "1_1") (pintype "passive"))
      (node (ref "C25") (pin "1") (pinfunction "1_1") (pintype "passive"))
      (node (ref "C26") (pin "1") (pinfunction "1_1") (pintype "passive"))
      (node (ref "C27") (pin "1") (pinfunction "1_1") (pintype "passive"))
      (node (ref "C28") (pin "1") (pinfunction "1_1") (pintype "passive"))
      (node (ref "C29") (pin "1") (pinfunction "1_1") (pintype "passive"))
      (node (ref "C30") (pin "1") (pinfunction "1_1") (pintype "passive"))
      (node (ref "C31") (pin "1") (pinfunction "1_1") (pintype "passive"))
      (node (ref "C32") (pin "1") (pinfunction "1_1") (pintype "passive"))
      (node (ref "C34") (pin "1") (pinfunction "1_1") (pintype "passive"))
      (node (ref "C35") (pin "2") (pinfunction "2_2") (pintype "passive"))
      (node (ref "C36") (pin "1") (pinfunction "1_1") (pintype "passive"))
      (node (ref "C37") (pin "1") (pinfunction "1_1") (pintype "passive"))
      (node (ref "C39") (pin "2") (pinfunction "2_2") (pintype "passive"))
      (node (ref "C40") (pin "1") (pinfunction "1_1") (pintype "passive"))
      (node (ref "C41") (pin "1") (pinfunction "1_1") (pintype "passive"))
      (node (ref "C42") (pin "1") (pinfunction "1_1") (pintype "passive"))
      (node (ref "C43") (pin "1") (pinfunction "1_1") (pintype "passive"))
      (node (ref "C44") (pin "1") (pinfunction "1_1") (pintype "passive"))
      (node (ref "C45") (pin "1") (pinfunction "1_1") (pintype "passive"))
      (node (ref "C76") (pin "1") (pinfunction "1_1") (pintype "passive"))
      (node (ref "C82") (pin "1") (pinfunction "1_1") (pintype "passive"))
      (node (ref "C84") (pin "1") (pinfunction "1_1") (pintype "passive"))
      (node (ref "C85") (pin "2") (pinfunction "2_2") (pintype "passive"))
      (node (ref "C86") (pin "2") (pinfunction "2_2") (pintype "passive"))
      (node (ref "D10") (pin "1") (pinfunction "A_1") (pintype "passive"))
      (node (ref "D25") (pin "2") (pinfunction "K_2") (pintype "passive"))
      (node (ref "D26") (pin "2") (pinfunction "K_2") (pintype "passive"))
      (node (ref "D8") (pin "1") (pinfunction "A_1") (pintype "passive"))
      (node (ref "D9") (pin "3") (pinfunction "A_3") (pintype "passive"))
      (node (ref "HD1") (pin "1") (pinfunction "1_1") (pintype "passive"))
      (node (ref "J4") (pin "1") (pinfunction "1_1") (pintype "passive"))
      (node (ref "J7") (pin "1") (pinfunction "1_1") (pintype "passive"))
      (node (ref "P1") (pin "9") (pinfunction "9_9") (pintype "passive"))
      (node (ref "P10") (pin "6") (pinfunction "6_6") (pintype "passive"))
      (node (ref "P2") (pin "3") (pinfunction "3_3") (pintype "passive"))
      (node (ref "P4") (pin "2") (pinfunction "2_2") (pintype "passive"))
      (node (ref "P4") (pin "6") (pinfunction "6_6") (pintype "passive"))
      (node (ref "P7") (pin "6") (pinfunction "6_6") (pintype "passive"))
      (node (ref "Q1") (pin "2") (pinfunction "S_2") (pintype "passive"))
      (node (ref "Q12") (pin "2") (pinfunction "E_2") (pintype "passive"))
      (node (ref "Q13") (pin "2") (pinfunction "E_2") (pintype "passive"))
      (node (ref "Q14") (pin "2") (pinfunction "E_2") (pintype "passive"))
      (node (ref "Q15") (pin "2") (pinfunction "E_2") (pintype "passive"))
      (node (ref "Q16") (pin "2") (pinfunction "E_2") (pintype "passive"))
      (node (ref "Q17") (pin "2") (pinfunction "E_2") (pintype "passive"))
      (node (ref "Q18") (pin "2") (pinfunction "E_2") (pintype "passive"))
      (node (ref "Q2") (pin "2") (pinfunction "E_2") (pintype "passive"))
      (node (ref "Q3") (pin "2") (pinfunction "E_2") (pintype "passive"))
      (node (ref "Q4") (pin "2") (pinfunction "E_2") (pintype "passive"))
      (node (ref "Q6") (pin "2") (pinfunction "E_2") (pintype "passive"))
      (node (ref "Q9") (pin "2") (pinfunction "E_2") (pintype "passive"))
      (node (ref "R10") (pin "2") (pinfunction "2_2") (pintype "passive"))
      (node (ref "R120") (pin "2") (pinfunction "2_2") (pintype "passive"))
      (node (ref "R123") (pin "2") (pinfunction "2_2") (pintype "passive"))
      (node (ref "R127") (pin "2") (pinfunction "2_2") (pintype "passive"))
      (node (ref "R128") (pin "2") (pinfunction "2_2") (pintype "passive"))
      (node (ref "R22") (pin "2") (pinfunction "2_2") (pintype "passive"))
      (node (ref "R26") (pin "2") (pinfunction "2_2") (pintype "passive"))
      (node (ref "R30") (pin "2") (pinfunction "2_2") (pintype "passive"))
      (node (ref "R51") (pin "2") (pinfunction "2_2") (pintype "passive"))
      (node (ref "R53") (pin "2") (pinfunction "2_2") (pintype "passive"))
      (node (ref "R68") (pin "2") (pinfunction "2_2") (pintype "passive"))
      (node (ref "R69") (pin "2") (pinfunction "2_2") (pintype "passive"))
      (node (ref "R79") (pin "2") (pinfunction "2_2") (pintype "passive"))
      (node (ref "R80") (pin "2") (pinfunction "2_2") (pintype "passive"))
      (node (ref "R85") (pin "2") (pinfunction "2_2") (pintype "passive"))
      (node (ref "U4") (pin "1") (pinfunction "GND_1") (pintype "power_in"))
      (node (ref "U8") (pin "4") (pinfunction "-V_4") (pintype "passive"))
      (node (ref "Z1") (pin "2") (pinfunction "A_2") (pintype "passive"))
      (node (ref "Z2") (pin "2") (pinfunction "A_2") (pintype "passive"))
      (node (ref "Z3") (pin "2") (pinfunction "A_2") (pintype "passive"))
      (node (ref "Z4") (pin "2") (pinfunction "A_2") (pintype "passive"))
      (node (ref "Z5") (pin "2") (pinfunction "A_2") (pintype "passive"))
      (node (ref "Z6") (pin "2") (pinfunction "A_2") (pintype "passive"))
      (node (ref "Z7") (pin "2") (pinfunction "A_2") (pintype "passive"))
      (node (ref "Z8") (pin "2") (pinfunction "A_2") (pintype "passive"))
    )
    (net (code "91") (name "Net-(C32-Pad2)") (class "Default")
      (node (ref "C32") (pin "2") (pinfunction "2_2") (pintype "passive"))
      (node (ref "F2") (pin "2") (pinfunction "2_2") (pintype "passive"))
      (node (ref "P1") (pin "10") (pinfunction "10_10") (pintype "passive"))
    )
    (net (code "92") (name "Net-(D3-A)") (class "Default")
      (node (ref "D3") (pin "1") (pinfunction "A_1") (pintype "passive"))
      (node (ref "R10") (pin "1") (pinfunction "1_1") (pintype "passive"))
      (node (ref "R11") (pin "2") (pinfunction "2_2") (pintype "passive"))
      (node (ref "R6") (pin "2") (pinfunction "2_2") (pintype "passive"))
      (node (ref "R8") (pin "2") (pinfunction "2_2") (pintype "passive"))
    )
    (net (code "93") (name "Net-(D6-A)") (class "Default")
      (node (ref "D6") (pin "1") (pinfunction "A_1") (pintype "passive"))
      (node (ref "R18") (pin "2") (pinfunction "2_2") (pintype "passive"))
      (node (ref "R20") (pin "2") (pinfunction "2_2") (pintype "passive"))
      (node (ref "R22") (pin "1") (pinfunction "1_1") (pintype "passive"))
      (node (ref "R23") (pin "2") (pinfunction "2_2") (pintype "passive"))
    )
    (net (code "94") (name "Net-(D7-A)") (class "Default")
      (node (ref "D7") (pin "1") (pinfunction "A_1") (pintype "passive"))
      (node (ref "R27") (pin "2") (pinfunction "2_2") (pintype "passive"))
      (node (ref "R28") (pin "2") (pinfunction "2_2") (pintype "passive"))
      (node (ref "R30") (pin "1") (pinfunction "1_1") (pintype "passive"))
      (node (ref "R31") (pin "2") (pinfunction "2_2") (pintype "passive"))
    )
    (net (code "95") (name "Net-(D11-A)") (class "Default")
      (node (ref "D11") (pin "1") (pinfunction "A_1") (pintype "passive"))
      (node (ref "R64") (pin "2") (pinfunction "2_2") (pintype "passive"))
      (node (ref "R66") (pin "2") (pinfunction "2_2") (pintype "passive"))
      (node (ref "R68") (pin "1") (pinfunction "1_1") (pintype "passive"))
      (node (ref "R70") (pin "2") (pinfunction "2_2") (pintype "passive"))
    )
    (net (code "96") (name "Net-(D12-A)") (class "Default")
      (node (ref "D12") (pin "1") (pinfunction "A_1") (pintype "passive"))
      (node (ref "R65") (pin "2") (pinfunction "2_2") (pintype "passive"))
      (node (ref "R67") (pin "2") (pinfunction "2_2") (pintype "passive"))
      (node (ref "R69") (pin "1") (pinfunction "1_1") (pintype "passive"))
      (node (ref "R71") (pin "2") (pinfunction "2_2") (pintype "passive"))
    )
    (net (code "97") (name "Net-(D13-A)") (class "Default")
      (node (ref "D13") (pin "1") (pinfunction "A_1") (pintype "passive"))
      (node (ref "K1") (pin "5") (pinfunction "COIL_2_5") (pintype "passive"))
      (node (ref "Q13") (pin "3") (pinfunction "C_3") (pintype "passive"))
    )
    (net (code "98") (name "Net-(D14-A)") (class "Default")
      (node (ref "D14") (pin "1") (pinfunction "A_1") (pintype "passive"))
      (node (ref "K2") (pin "5") (pinfunction "COIL_2_5") (pintype "passive"))
      (node (ref "Q14") (pin "3") (pinfunction "C_3") (pintype "passive"))
    )
    (net (code "99") (name "Net-(D15-A)") (class "Default")
      (node (ref "D15") (pin "1") (pinfunction "A_1") (pintype "passive"))
      (node (ref "K3") (pin "5") (pinfunction "COIL_2_5") (pintype "passive"))
      (node (ref "Q15") (pin "3") (pinfunction "C_3") (pintype "passive"))
    )
    (net (code "100") (name "Net-(D16-A)") (class "Default")
      (node (ref "D16") (pin "1") (pinfunction "A_1") (pintype "passive"))
      (node (ref "R72") (pin "2") (pinfunction "2_2") (pintype "passive"))
      (node (ref "R74") (pin "2") (pinfunction "2_2") (pintype "passive"))
      (node (ref "R79") (pin "1") (pinfunction "1_1") (pintype "passive"))
      (node (ref "R81") (pin "2") (pinfunction "2_2") (pintype "passive"))
    )
    (net (code "101") (name "Net-(D17-A)") (class "Default")
      (node (ref "D17") (pin "1") (pinfunction "A_1") (pintype "passive"))
      (node (ref "R73") (pin "2") (pinfunction "2_2") (pintype "passive"))
      (node (ref "R75") (pin "2") (pinfunction "2_2") (pintype "passive"))
      (node (ref "R80") (pin "1") (pinfunction "1_1") (pintype "passive"))
      (node (ref "R82") (pin "2") (pinfunction "2_2") (pintype "passive"))
    )
    (net (code "102") (name "Net-(D18-A)") (class "Default")
      (node (ref "D18") (pin "1") (pinfunction "A_1") (pintype "passive"))
      (node (ref "R83") (pin "2") (pinfunction "2_2") (pintype "passive"))
      (node (ref "R84") (pin "2") (pinfunction "2_2") (pintype "passive"))
      (node (ref "R85") (pin "1") (pinfunction "1_1") (pintype "passive"))
      (node (ref "R86") (pin "2") (pinfunction "2_2") (pintype "passive"))
    )
    (net (code "103") (name "Net-(D19-A)") (class "Default")
      (node (ref "D19") (pin "1") (pinfunction "A_1") (pintype "passive"))
      (node (ref "K4") (pin "5") (pinfunction "COIL_2_5") (pintype "passive"))
      (node (ref "Q16") (pin "3") (pinfunction "C_3") (pintype "passive"))
    )
    (net (code "104") (name "Net-(D20-A)") (class "Default")
      (node (ref "D20") (pin "1") (pinfunction "A_1") (pintype "passive"))
      (node (ref "K5") (pin "5") (pinfunction "COIL_2_5") (pintype "passive"))
      (node (ref "Q17") (pin "3") (pinfunction "C_3") (pintype "passive"))
    )
    (net (code "105") (name "Net-(D21-A)") (class "Default")
      (node (ref "D21") (pin "1") (pinfunction "A_1") (pintype "passive"))
      (node (ref "K6") (pin "5") (pinfunction "COIL_2_5") (pintype "passive"))
      (node (ref "Q18") (pin "3") (pinfunction "C_3") (pintype "passive"))
    )
    (net (code "106") (name "Net-(L4-A)") (class "Default")
      (node (ref "C38") (pin "2") (pinfunction "2_2") (pintype "passive"))
      (node (ref "L4") (pin "1") (pinfunction "A_1") (pintype "passive"))
      (node (ref "U4") (pin "2") (pinfunction "SW_2") (pintype "output"))
    )
    (net (code "107") (name "Net-(L5-Pad2)") (class "Default")
      (node (ref "L5") (pin "2") (pinfunction "2_2") (pintype "passive"))
      (node (ref "P4") (pin "1") (pinfunction "1_1") (pintype "passive"))
    )
    (net (code "108") (name "Net-(P3-Pad4)") (class "Default")
      (node (ref "P3") (pin "4") (pinfunction "4_4") (pintype "passive"))
      (node (ref "R39") (pin "1") (pinfunction "1_1") (pintype "passive"))
    )
    (net (code "109") (name "Net-(P3-Pad5)") (class "Default")
      (node (ref "P3") (pin "5") (pinfunction "5_5") (pintype "passive"))
      (node (ref "R40") (pin "1") (pinfunction "1_1") (pintype "passive"))
    )
    (net (code "110") (name "Net-(P3-Pad6)") (class "Default")
      (node (ref "P3") (pin "6") (pinfunction "6_6") (pintype "passive"))
      (node (ref "R41") (pin "1") (pinfunction "1_1") (pintype "passive"))
    )
    (net (code "111") (name "Net-(Q1-D)") (class "Default")
      (node (ref "Q1") (pin "3") (pinfunction "D_3") (pintype "passive"))
      (node (ref "R19") (pin "2") (pinfunction "2_2") (pintype "passive"))
    )
    (net (code "112") (name "Net-(Q1-G)") (class "Default")
      (node (ref "Q1") (pin "1") (pinfunction "G_1") (pintype "passive"))
      (node (ref "R25") (pin "1") (pinfunction "1_1") (pintype "passive"))
      (node (ref "R26") (pin "1") (pinfunction "1_1") (pintype "passive"))
    )
    (net (code "113") (name "Net-(Q2-B)") (class "Default")
      (node (ref "Q2") (pin "1") (pinfunction "B_1") (pintype "passive"))
      (node (ref "R42") (pin "1") (pinfunction "1_1") (pintype "passive"))
    )
    (net (code "114") (name "Net-(Q2-C)") (class "Default")
      (node (ref "Q2") (pin "3") (pinfunction "C_3") (pintype "passive"))
      (node (ref "R40") (pin "2") (pinfunction "2_2") (pintype "passive"))
    )
    (net (code "115") (name "Net-(Q3-B)") (class "Default")
      (node (ref "Q3") (pin "1") (pinfunction "B_1") (pintype "passive"))
      (node (ref "R43") (pin "1") (pinfunction "1_1") (pintype "passive"))
    )
    (net (code "116") (name "Net-(Q3-C)") (class "Default")
      (node (ref "Q3") (pin "3") (pinfunction "C_3") (pintype "passive"))
      (node (ref "R39") (pin "2") (pinfunction "2_2") (pintype "passive"))
    )
    (net (code "117") (name "Net-(Q4-B)") (class "Default")
      (node (ref "Q4") (pin "1") (pinfunction "B_1") (pintype "passive"))
      (node (ref "R44") (pin "1") (pinfunction "1_1") (pintype "passive"))
    )
    (net (code "118") (name "Net-(Q4-C)") (class "Default")
      (node (ref "Q4") (pin "3") (pinfunction "C_3") (pintype "passive"))
      (node (ref "R41") (pin "2") (pinfunction "2_2") (pintype "passive"))
    )
    (net (code "119") (name "Net-(Q5-D)") (class "Default")
      (node (ref "C34") (pin "2") (pinfunction "2_2") (pintype "passive"))
      (node (ref "C76") (pin "2") (pinfunction "2_2") (pintype "passive"))
      (node (ref "Q5") (pin "2") (pinfunction "D_2") (pintype "passive"))
      (node (ref "R46") (pin "2") (pinfunction "2_2") (pintype "passive"))
      (node (ref "U4") (pin "3") (pinfunction "VIN_3") (pintype "power_in"))
    )
    (net (code "120") (name "Net-(Q5-G)") (class "Default")
      (node (ref "Q5") (pin "1") (pinfunction "G_1") (pintype "passive"))
      (node (ref "Q6") (pin "3") (pinfunction "C_3") (pintype "passive"))
      (node (ref "R45") (pin "2") (pinfunction "2_2") (pintype "passive"))
    )
    (net (code "121") (name "Net-(Q6-B)") (class "Default")
      (node (ref "Q6") (pin "1") (pinfunction "B_1") (pintype "passive"))
      (node (ref "R50") (pin "1") (pinfunction "1_1") (pintype "passive"))
    )
    (net (code "122") (name "Net-(Q7-B)") (class "Default")
      (node (ref "Q7") (pin "1") (pinfunction "B_1") (pintype "passive"))
      (node (ref "R52") (pin "2") (pinfunction "2_2") (pintype "passive"))
    )
    (net (code "123") (name "Net-(Q7-E)") (class "Default")
      (node (ref "Q7") (pin "2") (pinfunction "E_2") (pintype "passive"))
      (node (ref "R54") (pin "2") (pinfunction "2_2") (pintype "passive"))
      (node (ref "R59") (pin "1") (pinfunction "1_1") (pintype "passive"))
    )
    (net (code "124") (name "Net-(Q8-G)") (class "Default")
      (node (ref "Q8") (pin "1") (pinfunction "G_1") (pintype "passive"))
      (node (ref "Q9") (pin "3") (pinfunction "C_3") (pintype "passive"))
      (node (ref "R57") (pin "2") (pinfunction "2_2") (pintype "passive"))
    )
    (net (code "125") (name "Net-(Q9-B)") (class "Default")
      (node (ref "Q9") (pin "1") (pinfunction "B_1") (pintype "passive"))
      (node (ref "R61") (pin "1") (pinfunction "1_1") (pintype "passive"))
    )
    (net (code "126") (name "Net-(Q10-B)") (class "Default")
      (node (ref "Q10") (pin "1") (pinfunction "B_1") (pintype "passive"))
      (node (ref "R56") (pin "2") (pinfunction "2_2") (pintype "passive"))
    )
    (net (code "127") (name "Net-(Q10-C)") (class "Default")
      (node (ref "Q10") (pin "3") (pinfunction "C_3") (pintype "passive"))
      (node (ref "R58") (pin "2") (pinfunction "2_2") (pintype "passive"))
      (node (ref "R60") (pin "1") (pinfunction "1_1") (pintype "passive"))
    )
    (net (code "128") (name "Net-(Q11-G)") (class "Default")
      (node (ref "Q11") (pin "1") (pinfunction "G_1") (pintype "passive"))
      (node (ref "Q12") (pin "3") (pinfunction "C_3") (pintype "passive"))
      (node (ref "R62") (pin "2") (pinfunction "2_2") (pintype "passive"))
    )
    (net (code "129") (name "Net-(Q12-B)") (class "Default")
      (node (ref "Q12") (pin "1") (pinfunction "B_1") (pintype "passive"))
      (node (ref "R63") (pin "1") (pinfunction "1_1") (pintype "passive"))
    )
    (net (code "130") (name "Net-(Q13-B)") (class "Default")
      (node (ref "Q13") (pin "1") (pinfunction "B_1") (pintype "passive"))
      (node (ref "R76") (pin "1") (pinfunction "1_1") (pintype "passive"))
    )
    (net (code "131") (name "Net-(Q14-B)") (class "Default")
      (node (ref "Q14") (pin "1") (pinfunction "B_1") (pintype "passive"))
      (node (ref "R77") (pin "1") (pinfunction "1_1") (pintype "passive"))
    )
    (net (code "132") (name "Net-(Q15-B)") (class "Default")
      (node (ref "Q15") (pin "1") (pinfunction "B_1") (pintype "passive"))
      (node (ref "R78") (pin "1") (pinfunction "1_1") (pintype "passive"))
    )
    (net (code "133") (name "Net-(Q16-B)") (class "Default")
      (node (ref "Q16") (pin "1") (pinfunction "B_1") (pintype "passive"))
      (node (ref "R87") (pin "1") (pinfunction "1_1") (pintype "passive"))
    )
    (net (code "134") (name "Net-(Q17-B)") (class "Default")
      (node (ref "Q17") (pin "1") (pinfunction "B_1") (pintype "passive"))
      (node (ref "R88") (pin "1") (pinfunction "1_1") (pintype "passive"))
    )
    (net (code "135") (name "Net-(Q18-B)") (class "Default")
      (node (ref "Q18") (pin "1") (pinfunction "B_1") (pintype "passive"))
      (node (ref "R89") (pin "1") (pinfunction "1_1") (pintype "passive"))
    )
    (net (code "136") (name "Net-(R49-TOP)") (class "Default")
      (node (ref "R48") (pin "2") (pinfunction "2_2") (pintype "passive"))
      (node (ref "R49") (pin "1") (pinfunction "TOP_1") (pintype "passive"))
    )
    (net (code "137") (name "Net-(U4-EN)") (class "Default")
      (node (ref "R46") (pin "1") (pinfunction "1_1") (pintype "passive"))
      (node (ref "R51") (pin "1") (pinfunction "1_1") (pintype "passive"))
      (node (ref "U4") (pin "5") (pinfunction "EN_5") (pintype "input"))
    )
    (net (code "138") (name "Net-(U4-VBST)") (class "Default")
      (node (ref "C38") (pin "1") (pinfunction "1_1") (pintype "passive"))
      (node (ref "U4") (pin "6") (pinfunction "VBST_6") (pintype "output"))
    )
    (net (code "139") (name "Net-(U4-VFB)") (class "Default")
      (node (ref "R47") (pin "1") (pinfunction "1_1") (pintype "passive"))
      (node (ref "R48") (pin "1") (pinfunction "1_1") (pintype "passive"))
      (node (ref "R53") (pin "1") (pinfunction "1_1") (pintype "passive"))
      (node (ref "U4") (pin "4") (pinfunction "VFB_4") (pintype "input"))
    )
    (net (code "140") (name "Net-(U8A-IN+)") (class "Default")
      (node (ref "R122") (pin "1") (pinfunction "1_1") (pintype "passive"))
      (node (ref "U8") (pin "3") (pinfunction "IN+_3") (pintype "passive"))
    )
    (net (code "141") (name "Net-(U8A-IN-)") (class "Default")
      (node (ref "C81") (pin "2") (pinfunction "2_2") (pintype "passive"))
      (node (ref "R119") (pin "1") (pinfunction "1_1") (pintype "passive"))
      (node (ref "R120") (pin "1") (pinfunction "1_1") (pintype "passive"))
      (node (ref "U8") (pin "2") (pinfunction "IN-_2") (pintype "passive"))
    )
    (net (code "142") (name "Net-(U8B-IN+)") (class "Default")
      (node (ref "R126") (pin "1") (pinfunction "1_1") (pintype "passive"))
      (node (ref "U8") (pin "5") (pinfunction "IN+_5") (pintype "passive"))
    )
    (net (code "143") (name "Net-(U8B-IN-)") (class "Default")
      (node (ref "C83") (pin "2") (pinfunction "2_2") (pintype "passive"))
      (node (ref "R123") (pin "1") (pinfunction "1_1") (pintype "passive"))
      (node (ref "R124") (pin "1") (pinfunction "1_1") (pintype "passive"))
      (node (ref "U8") (pin "6") (pinfunction "IN-_6") (pintype "passive"))
    )
    (net (code "144") (name "Net-(U8B-OUT)") (class "Default")
      (node (ref "C83") (pin "1") (pinfunction "1_1") (pintype "passive"))
      (node (ref "R124") (pin "2") (pinfunction "2_2") (pintype "passive"))
      (node (ref "R125") (pin "2") (pinfunction "2_2") (pintype "passive"))
      (node (ref "U8") (pin "7") (pinfunction "OUT_7") (pintype "passive"))
    )
    (net (code "145") (name "V_motor") (class "Default")
      (node (ref "C35") (pin "1") (pinfunction "1_1") (pintype "passive"))
      (node (ref "C36") (pin "2") (pinfunction "2_2") (pintype "passive"))
      (node (ref "C37") (pin "2") (pinfunction "2_2") (pintype "passive"))
      (node (ref "L4") (pin "2") (pinfunction "B_2") (pintype "passive"))
      (node (ref "P10") (pin "2") (pinfunction "2_2") (pintype "passive"))
      (node (ref "R47") (pin "2") (pinfunction "2_2") (pintype "passive"))
      (node (ref "R49") (pin "2") (pinfunction "BOT_2") (pintype "passive"))
      (node (ref "R49") (pin "3") (pinfunction "TAP_3") (pintype "passive"))
    )
    (net (code "146") (name "unconnected-(HD1-Pad3)") (class "Default")
      (node (ref "HD1") (pin "3") (pinfunction "3_3") (pintype "passive+no_connect"))
    )
    (net (code "147") (name "unconnected-(HD1-Pad9)") (class "Default")
      (node (ref "HD1") (pin "9") (pinfunction "9_9") (pintype "passive+no_connect"))
    )
    (net (code "148") (name "unconnected-(HD1-Pad10)") (class "Default")
      (node (ref "HD1") (pin "10") (pinfunction "10_10") (pintype "passive+no_connect"))
    )
    (net (code "149") (name "unconnected-(HD1-Pad11)") (class "Default")
      (node (ref "HD1") (pin "11") (pinfunction "11_11") (pintype "passive+no_connect"))
    )
    (net (code "150") (name "unconnected-(HD1-Pad12)") (class "Default")
      (node (ref "HD1") (pin "12") (pinfunction "12_12") (pintype "passive+no_connect"))
    )
    (net (code "151") (name "unconnected-(HD1-Pad13)") (class "Default")
      (node (ref "HD1") (pin "13") (pinfunction "13_13") (pintype "passive+no_connect"))
    )
    (net (code "152") (name "unconnected-(HD1-Pad14)") (class "Default")
      (node (ref "HD1") (pin "14") (pinfunction "14_14") (pintype "passive+no_connect"))
    )
    (net (code "153") (name "unconnected-(HD1-Pad15)") (class "Default")
      (node (ref "HD1") (pin "15") (pinfunction "15_15") (pintype "passive+no_connect"))
    )
    (net (code "154") (name "unconnected-(HD1-Pad16)") (class "Default")
      (node (ref "HD1") (pin "16") (pinfunction "16_16") (pintype "passive+no_connect"))
    )
    (net (code "155") (name "unconnected-(HD1-Pad18)") (class "Default")
      (node (ref "HD1") (pin "18") (pinfunction "18_18") (pintype "passive+no_connect"))
    )
    (net (code "156") (name "unconnected-(K1-NC-Pad4)") (class "Default")
      (node (ref "K1") (pin "4") (pinfunction "NC_4") (pintype "passive"))
    )
    (net (code "157") (name "unconnected-(K2-NC-Pad4)") (class "Default")
      (node (ref "K2") (pin "4") (pinfunction "NC_4") (pintype "passive"))
    )
    (net (code "158") (name "unconnected-(K3-NC-Pad4)") (class "Default")
      (node (ref "K3") (pin "4") (pinfunction "NC_4") (pintype "passive"))
    )
    (net (code "159") (name "unconnected-(K4-NC-Pad4)") (class "Default")
      (node (ref "K4") (pin "4") (pinfunction "NC_4") (pintype "passive"))
    )
    (net (code "160") (name "unconnected-(K5-NC-Pad4)") (class "Default")
      (node (ref "K5") (pin "4") (pinfunction "NC_4") (pintype "passive"))
    )
    (net (code "161") (name "unconnected-(K6-NC-Pad4)") (class "Default")
      (node (ref "K6") (pin "4") (pinfunction "NC_4") (pintype "passive"))
    )
    (net (code "162") (name "unconnected-(P2-Pad2)") (class "Default")
      (node (ref "P2") (pin "2") (pinfunction "2_2") (pintype "passive"))
    )
    (net (code "163") (name "unconnected-(P2-Pad5)") (class "Default")
      (node (ref "P2") (pin "5") (pinfunction "5_5") (pintype "passive"))
    )
    (net (code "164") (name "unconnected-(P2-Pad6)") (class "Default")
      (node (ref "P2") (pin "6") (pinfunction "6_6") (pintype "passive"))
    )
    (net (code "165") (name "unconnected-(P7-Pad1)") (class "Default")
      (node (ref "P7") (pin "1") (pinfunction "1_1") (pintype "passive+no_connect"))
    )
  )
)
